# ECG_NEMO_final.net
KiCad netlist of a schematic drawn in Altium Designer
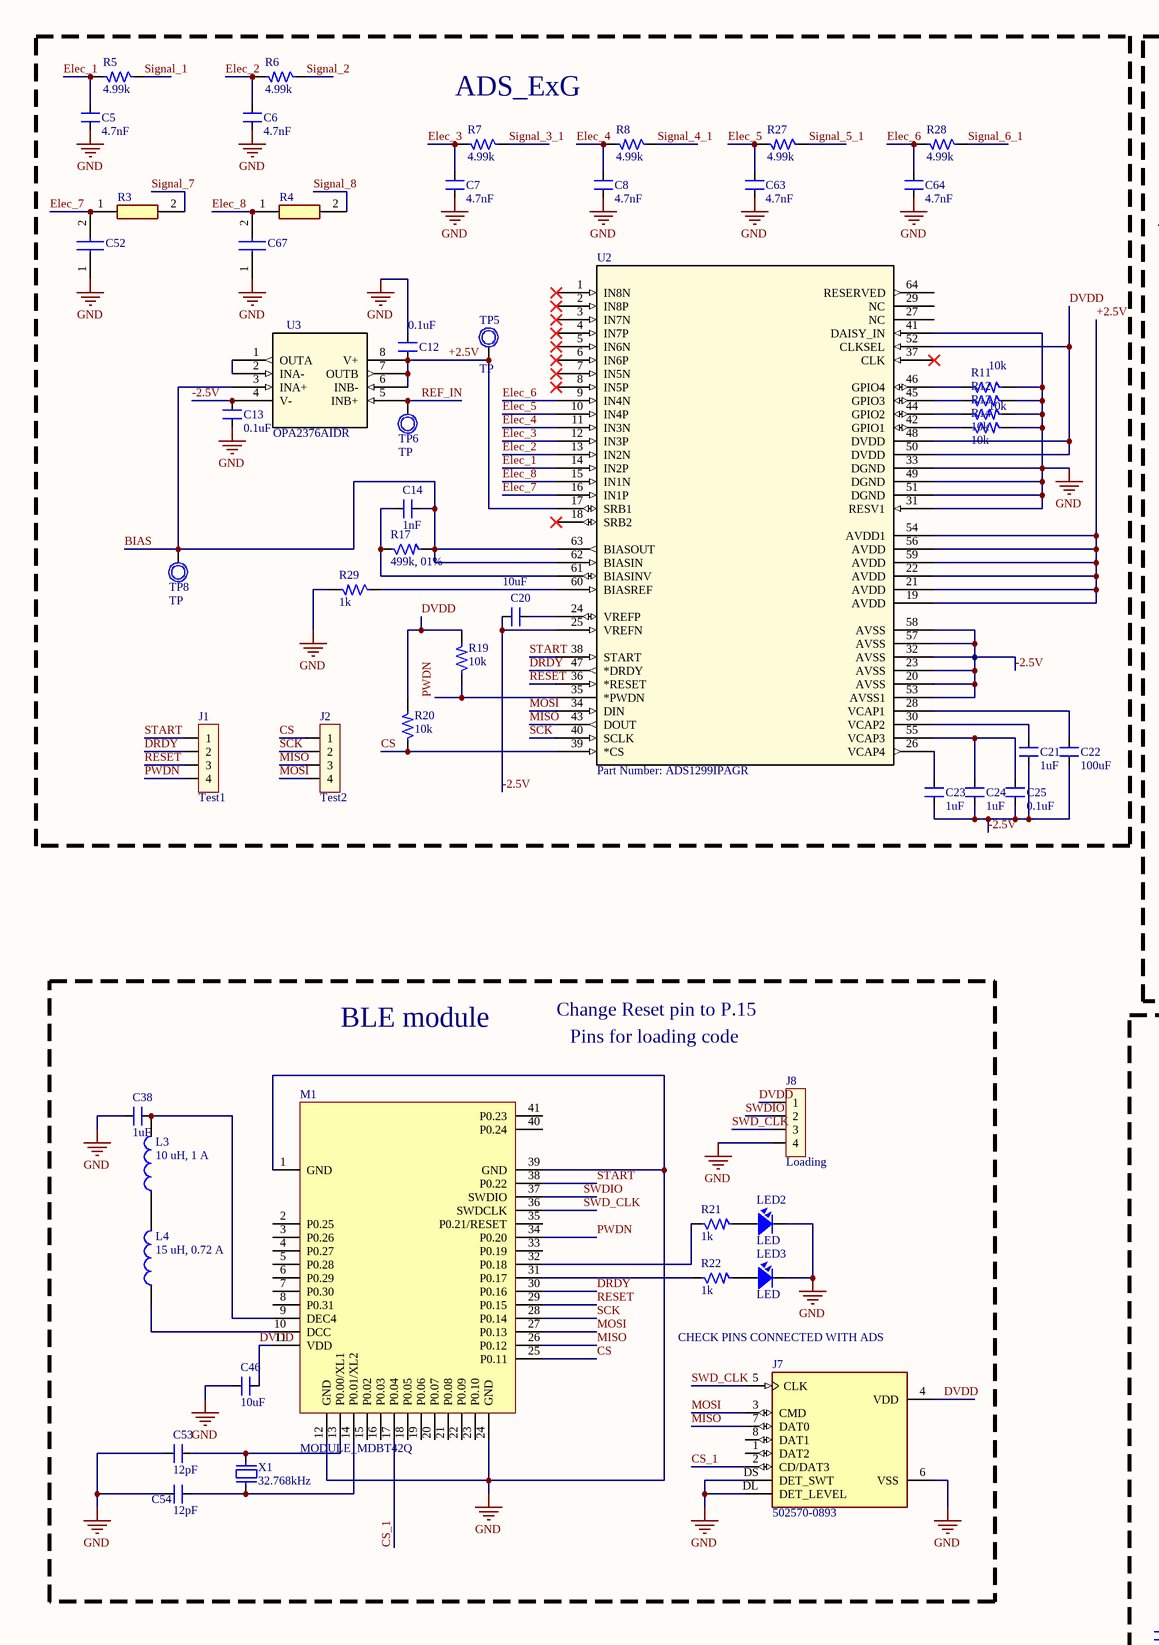
[diagram p0: ECG_NEMO_final.schdoc, left]
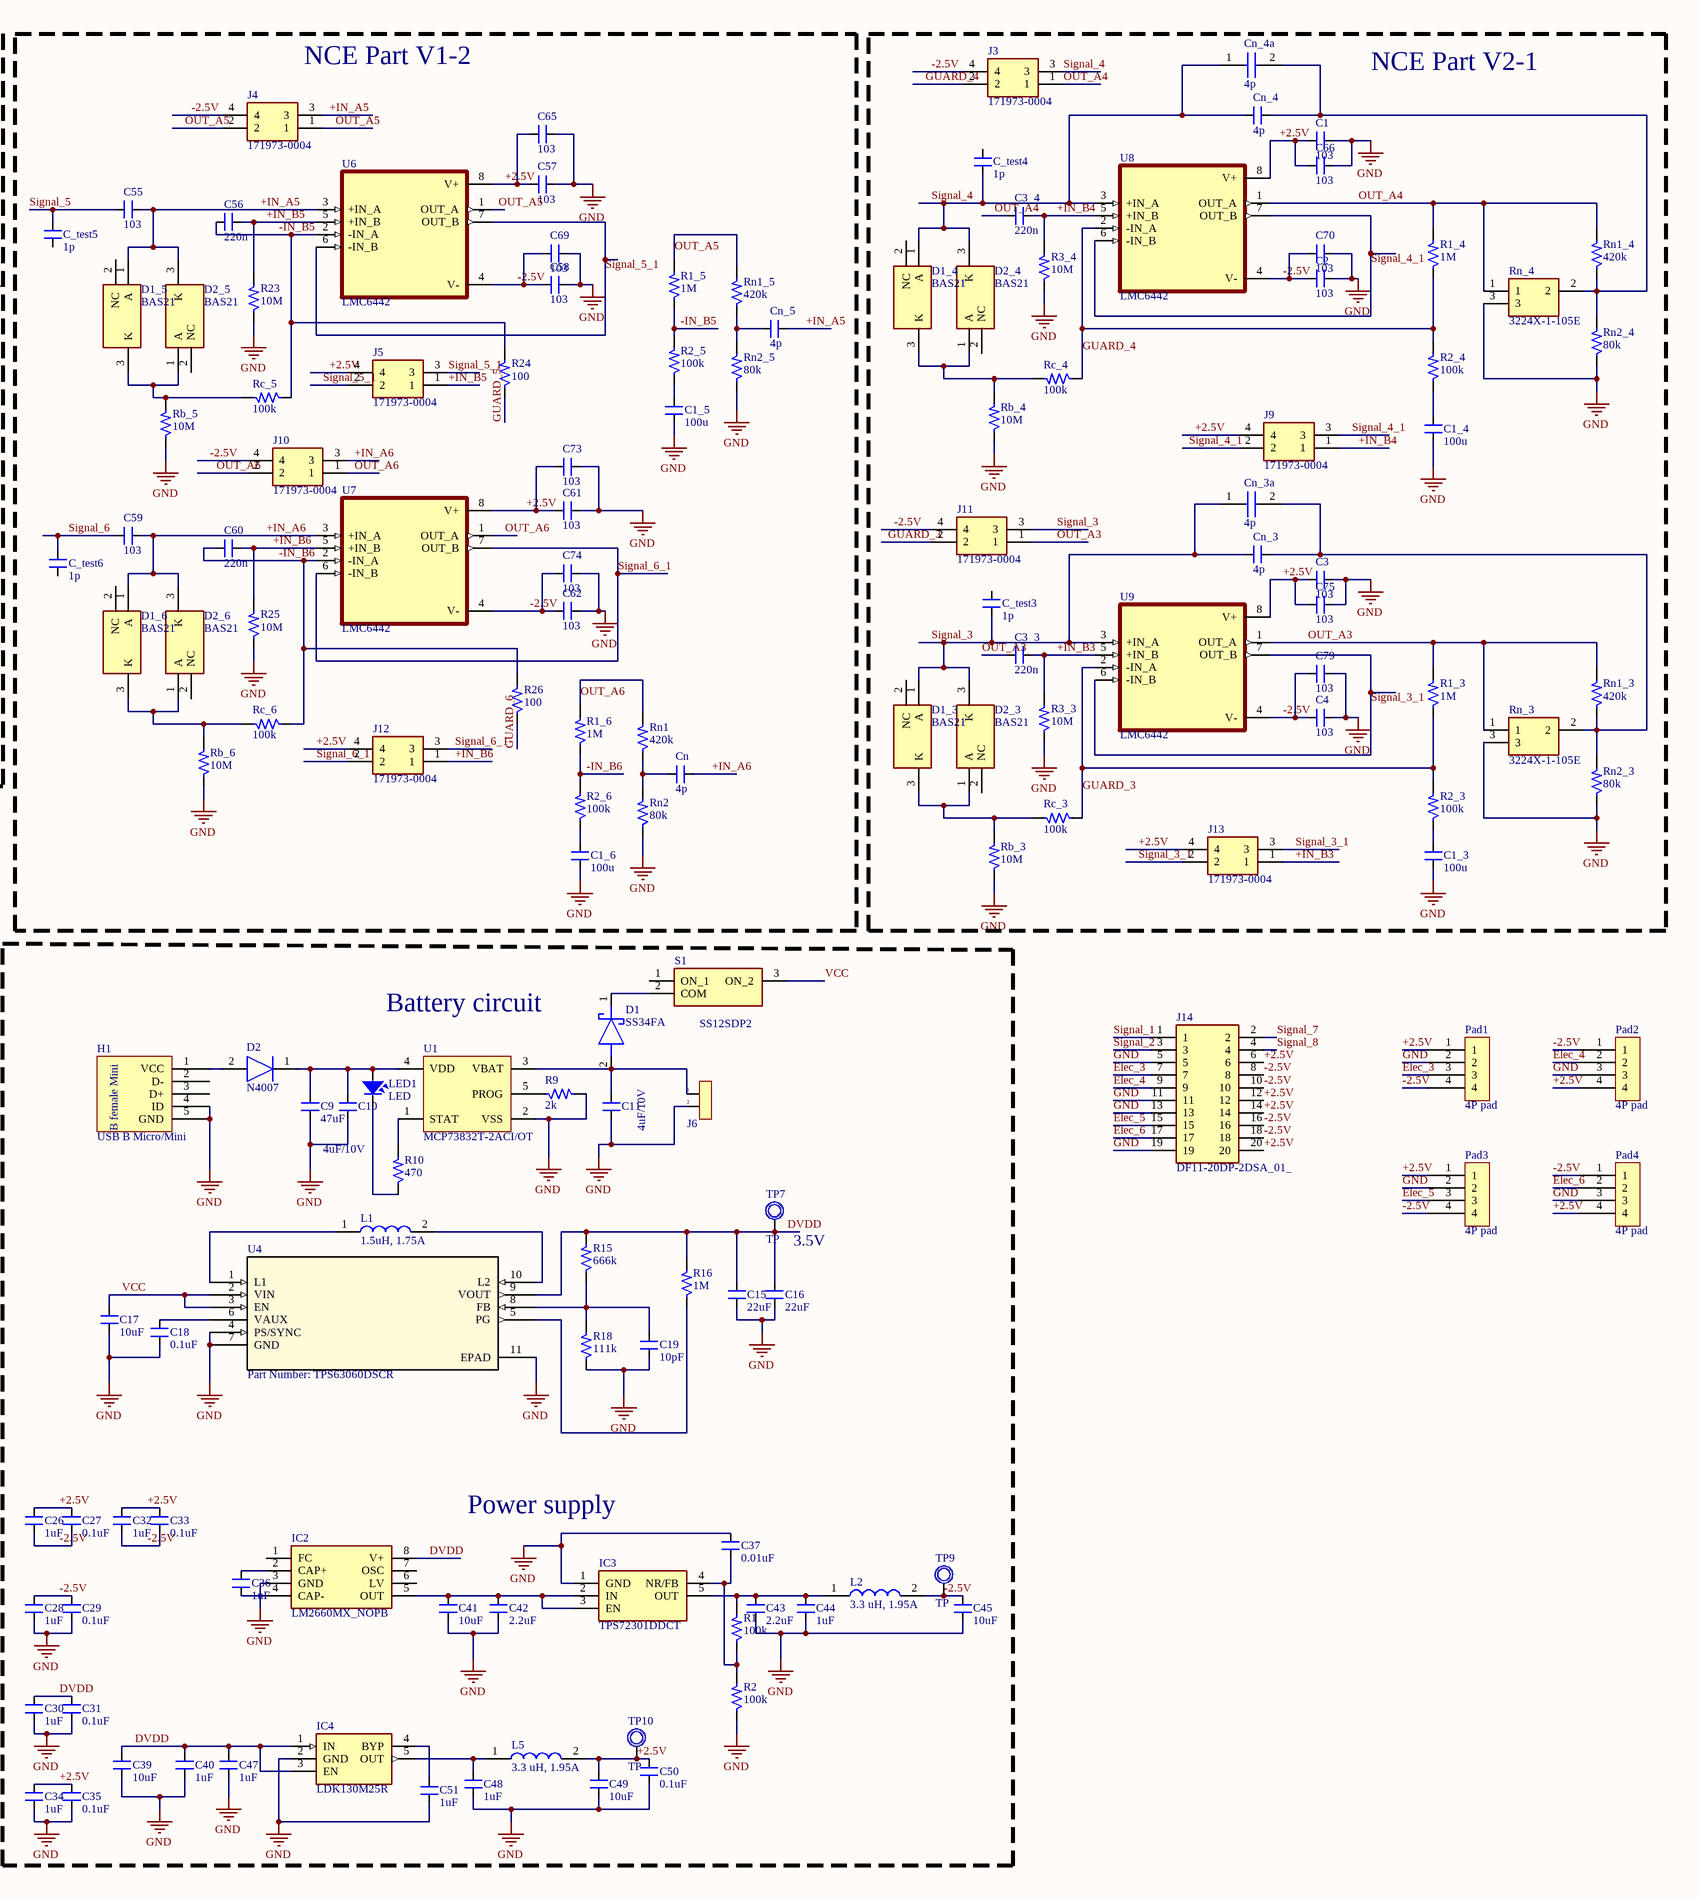
[diagram p1: ECG_NEMO_final.schdoc, right]

(export (version "E")
  (design (tool "Eeschema 10.0.6"))
  (components
    (comp (ref "C1")
      (value "103")
      (footprint "SM-0805")
      (description "Cap SMD")
      (libsource (lib "VioletofSun") (part "CM"))
    )
    (comp (ref "C1_3")
      (value "100u")
      (footprint "SM-0805")
      (description "Cap SMD")
      (libsource (lib "VioletofSun") (part "CM"))
    )
    (comp (ref "C1_4")
      (value "100u")
      (footprint "SM-0805")
      (description "Cap SMD")
      (libsource (lib "VioletofSun") (part "CM"))
    )
    (comp (ref "C1_5")
      (value "100u")
      (footprint "SM-0805")
      (description "Cap SMD")
      (libsource (lib "VioletofSun") (part "CM"))
    )
    (comp (ref "C1_6")
      (value "100u")
      (footprint "SM-0805")
      (description "Cap SMD")
      (libsource (lib "VioletofSun") (part "CM"))
    )
    (comp (ref "C2")
      (value "103")
      (footprint "SM-0805")
      (description "Cap SMD")
      (libsource (lib "VioletofSun") (part "CM"))
    )
    (comp (ref "C3")
      (value "103")
      (footprint "SM-0805")
      (description "Cap SMD")
      (libsource (lib "VioletofSun") (part "CM"))
    )
    (comp (ref "C3_3")
      (value "220n")
      (footprint "SM-0805")
      (description "Cap SMD")
      (libsource (lib "VioletofSun") (part "CM"))
    )
    (comp (ref "C3_4")
      (value "220n")
      (footprint "SM-0805")
      (description "Cap SMD")
      (libsource (lib "VioletofSun") (part "CM"))
    )
    (comp (ref "C4")
      (value "103")
      (footprint "SM-0805")
      (description "Cap SMD")
      (libsource (lib "VioletofSun") (part "CM"))
    )
    (comp (ref "C5")
      (value "4.7nF")
      (footprint "SM-0805")
      (description "Cap SMD")
      (libsource (lib "VioletofSun") (part "CM"))
    )
    (comp (ref "C6")
      (value "4.7nF")
      (footprint "SM-0805")
      (description "Cap SMD")
      (libsource (lib "VioletofSun") (part "CM"))
    )
    (comp (ref "C7")
      (value "4.7nF")
      (footprint "SM-0805")
      (description "Cap SMD")
      (libsource (lib "VioletofSun") (part "CM"))
    )
    (comp (ref "C8")
      (value "4.7nF")
      (footprint "SM-0805")
      (description "Cap SMD")
      (libsource (lib "VioletofSun") (part "CM"))
    )
    (comp (ref "C9")
      (value "47uF")
      (footprint "SM-0805")
      (description "Cap SMD")
      (libsource (lib "VioletofSun") (part "CM"))
    )
    (comp (ref "C10")
      (value "4uF/10V")
      (footprint "SM-0805")
      (description "Cap SMD")
      (libsource (lib "VioletofSun") (part "CM"))
    )
    (comp (ref "C11")
      (value "4uF/10V")
      (footprint "SM-0805")
      (description "Cap SMD")
      (libsource (lib "VioletofSun") (part "CM"))
    )
    (comp (ref "C12")
      (value "0.1uF")
      (footprint "SM-0805")
      (description "Cap SMD")
      (libsource (lib "VioletofSun") (part "CM"))
    )
    (comp (ref "C13")
      (value "0.1uF")
      (footprint "SM-0805")
      (description "Cap SMD")
      (libsource (lib "VioletofSun") (part "CM"))
    )
    (comp (ref "C14")
      (value "1nF")
      (footprint "SM-0805")
      (description "Cap SMD")
      (libsource (lib "VioletofSun") (part "CM"))
    )
    (comp (ref "C15")
      (value "22uF")
      (footprint "SM-0805")
      (description "Cap SMD")
      (libsource (lib "VioletofSun") (part "CM"))
    )
    (comp (ref "C16")
      (value "22uF")
      (footprint "SM-0805")
      (description "Cap SMD")
      (libsource (lib "VioletofSun") (part "CM"))
    )
    (comp (ref "C17")
      (value "10uF")
      (footprint "SM-0805")
      (description "Cap SMD")
      (libsource (lib "VioletofSun") (part "CM"))
    )
    (comp (ref "C18")
      (value "0.1uF")
      (footprint "SM-0805")
      (description "Cap SMD")
      (libsource (lib "VioletofSun") (part "CM"))
    )
    (comp (ref "C19")
      (value "10pF")
      (footprint "SM-0805")
      (description "Cap SMD")
      (libsource (lib "VioletofSun") (part "CM"))
    )
    (comp (ref "C20")
      (value "10uF")
      (footprint "SM-0805")
      (description "Cap SMD")
      (libsource (lib "VioletofSun") (part "CM"))
    )
    (comp (ref "C21")
      (value "1uF")
      (footprint "SM-0805")
      (description "Cap SMD")
      (libsource (lib "VioletofSun") (part "CM"))
    )
    (comp (ref "C22")
      (value "100uF")
      (footprint "SM-0805")
      (description "Cap SMD")
      (libsource (lib "VioletofSun") (part "CM"))
    )
    (comp (ref "C23")
      (value "1uF")
      (footprint "SM-0805")
      (description "Cap SMD")
      (libsource (lib "VioletofSun") (part "CM"))
    )
    (comp (ref "C24")
      (value "1uF")
      (footprint "SM-0805")
      (description "Cap SMD")
      (libsource (lib "VioletofSun") (part "CM"))
    )
    (comp (ref "C25")
      (value "0.1uF")
      (footprint "SM-0805")
      (description "Cap SMD")
      (libsource (lib "VioletofSun") (part "CM"))
    )
    (comp (ref "C26")
      (value "1uF")
      (footprint "SM-0805")
      (description "Cap SMD")
      (libsource (lib "VioletofSun") (part "CM"))
    )
    (comp (ref "C27")
      (value "0.1uF")
      (footprint "SM-0805")
      (description "Cap SMD")
      (libsource (lib "VioletofSun") (part "CM"))
    )
    (comp (ref "C28")
      (value "1uF")
      (footprint "SM-0805")
      (description "Cap SMD")
      (libsource (lib "VioletofSun") (part "CM"))
    )
    (comp (ref "C29")
      (value "0.1uF")
      (footprint "SM-0805")
      (description "Cap SMD")
      (libsource (lib "VioletofSun") (part "CM"))
    )
    (comp (ref "C30")
      (value "1uF")
      (footprint "SM-0805")
      (description "Cap SMD")
      (libsource (lib "VioletofSun") (part "CM"))
    )
    (comp (ref "C31")
      (value "0.1uF")
      (footprint "SM-0805")
      (description "Cap SMD")
      (libsource (lib "VioletofSun") (part "CM"))
    )
    (comp (ref "C32")
      (value "1uF")
      (footprint "SM-0805")
      (description "Cap SMD")
      (libsource (lib "VioletofSun") (part "CM"))
    )
    (comp (ref "C33")
      (value "0.1uF")
      (footprint "SM-0805")
      (description "Cap SMD")
      (libsource (lib "VioletofSun") (part "CM"))
    )
    (comp (ref "C34")
      (value "1uF")
      (footprint "SM-0805")
      (description "Cap SMD")
      (libsource (lib "VioletofSun") (part "CM"))
    )
    (comp (ref "C35")
      (value "0.1uF")
      (footprint "SM-0805")
      (description "Cap SMD")
      (libsource (lib "VioletofSun") (part "CM"))
    )
    (comp (ref "C36")
      (value "1uF")
      (footprint "SM-0805")
      (description "Cap SMD")
      (libsource (lib "VioletofSun") (part "CM"))
    )
    (comp (ref "C37")
      (value "0.01uF")
      (footprint "SM-0805")
      (description "Cap SMD")
      (libsource (lib "VioletofSun") (part "CM"))
    )
    (comp (ref "C38")
      (value "1uF")
      (footprint "SM-0805")
      (description "Cap SMD")
      (libsource (lib "VioletofSun") (part "CM"))
    )
    (comp (ref "C39")
      (value "10uF")
      (footprint "SM-0805")
      (description "Cap SMD")
      (libsource (lib "VioletofSun") (part "CM"))
    )
    (comp (ref "C40")
      (value "1uF")
      (footprint "SM-0805")
      (description "Cap SMD")
      (libsource (lib "VioletofSun") (part "CM"))
    )
    (comp (ref "C41")
      (value "10uF")
      (footprint "SM-0805")
      (description "Cap SMD")
      (libsource (lib "VioletofSun") (part "CM"))
    )
    (comp (ref "C42")
      (value "2.2uF")
      (footprint "SM-0805")
      (description "Cap SMD")
      (libsource (lib "VioletofSun") (part "CM"))
    )
    (comp (ref "C43")
      (value "2.2uF")
      (footprint "SM-0805")
      (description "Cap SMD")
      (libsource (lib "VioletofSun") (part "CM"))
    )
    (comp (ref "C44")
      (value "1uF")
      (footprint "SM-0805")
      (description "Cap SMD")
      (libsource (lib "VioletofSun") (part "CM"))
    )
    (comp (ref "C45")
      (value "10uF")
      (footprint "SM-0805")
      (description "Cap SMD")
      (libsource (lib "VioletofSun") (part "CM"))
    )
    (comp (ref "C46")
      (value "10uF")
      (footprint "SM-0805")
      (description "Cap SMD")
      (libsource (lib "VioletofSun") (part "CM"))
    )
    (comp (ref "C47")
      (value "1uF")
      (footprint "SM-0805")
      (description "Cap SMD")
      (libsource (lib "VioletofSun") (part "CM"))
    )
    (comp (ref "C48")
      (value "1uF")
      (footprint "SM-0805")
      (description "Cap SMD")
      (libsource (lib "VioletofSun") (part "CM"))
    )
    (comp (ref "C49")
      (value "10uF")
      (footprint "SM-0805")
      (description "Cap SMD")
      (libsource (lib "VioletofSun") (part "CM"))
    )
    (comp (ref "C50")
      (value "0.1uF")
      (footprint "SM-0805")
      (description "Cap SMD")
      (libsource (lib "VioletofSun") (part "CM"))
    )
    (comp (ref "C51")
      (value "1uF")
      (footprint "SM-0805")
      (description "Cap SMD")
      (libsource (lib "VioletofSun") (part "CM"))
    )
    (comp (ref "C52")
      (value "VJ0805Y472KXAMC")
      (footprint "SamacSys:CAPC2012X145N")
      (description "Capacitor 4.7nF")
      (fields (field (name "MOUSER PART NUMBER") "77-VJ0805Y472KXAMC"))
      (libsource (lib "SamacSys") (part "VJ0805Y472KXAMC"))
    )
    (comp (ref "C53")
      (value "12pF")
      (footprint "SM-0805")
      (description "Cap SMD")
      (libsource (lib "VioletofSun") (part "CM"))
    )
    (comp (ref "C54")
      (value "12pF")
      (footprint "SM-0805")
      (description "Cap SMD")
      (libsource (lib "VioletofSun") (part "CM"))
    )
    (comp (ref "C55")
      (value "103")
      (footprint "SM-0805")
      (description "Cap SMD")
      (libsource (lib "Free Documents") (part "CM_5"))
    )
    (comp (ref "C56")
      (value "220n")
      (footprint "SM-0805")
      (description "Cap SMD")
      (libsource (lib "VioletofSun") (part "CM"))
    )
    (comp (ref "C57")
      (value "103")
      (footprint "SM-0805")
      (description "Cap SMD")
      (libsource (lib "VioletofSun") (part "CM"))
    )
    (comp (ref "C58")
      (value "103")
      (footprint "SM-0805")
      (description "Cap SMD")
      (libsource (lib "VioletofSun") (part "CM"))
    )
    (comp (ref "C59")
      (value "103")
      (footprint "SM-0805")
      (description "Cap SMD")
      (libsource (lib "VioletofSun") (part "CM"))
    )
    (comp (ref "C60")
      (value "220n")
      (footprint "SM-0805")
      (description "Cap SMD")
      (libsource (lib "VioletofSun") (part "CM"))
    )
    (comp (ref "C61")
      (value "103")
      (footprint "SM-0805")
      (description "Cap SMD")
      (libsource (lib "VioletofSun") (part "CM"))
    )
    (comp (ref "C62")
      (value "103")
      (footprint "SM-0805")
      (description "Cap SMD")
      (libsource (lib "VioletofSun") (part "CM"))
    )
    (comp (ref "C63")
      (value "4.7nF")
      (footprint "SM-0805")
      (description "Cap SMD")
      (libsource (lib "VioletofSun") (part "CM"))
    )
    (comp (ref "C64")
      (value "4.7nF")
      (footprint "SM-0805")
      (description "Cap SMD")
      (libsource (lib "VioletofSun") (part "CM"))
    )
    (comp (ref "C65")
      (value "103")
      (footprint "SM-0805")
      (description "Cap SMD")
      (libsource (lib "VioletofSun") (part "CM"))
    )
    (comp (ref "C66")
      (value "103")
      (footprint "SM-0805")
      (description "Cap SMD")
      (libsource (lib "VioletofSun") (part "CM"))
    )
    (comp (ref "C67")
      (value "VJ0805Y472KXAMC")
      (footprint "SamacSys:CAPC2012X145N")
      (description "Capacitor 4.7nF")
      (fields (field (name "MOUSER PART NUMBER") "77-VJ0805Y472KXAMC"))
      (libsource (lib "SamacSys") (part "VJ0805Y472KXAMC"))
    )
    (comp (ref "C69")
      (value "103")
      (footprint "SM-0805")
      (description "Cap SMD")
      (libsource (lib "VioletofSun") (part "CM"))
    )
    (comp (ref "C70")
      (value "103")
      (footprint "SM-0805")
      (description "Cap SMD")
      (libsource (lib "VioletofSun") (part "CM"))
    )
    (comp (ref "C73")
      (value "103")
      (footprint "SM-0805")
      (description "Cap SMD")
      (libsource (lib "VioletofSun") (part "CM"))
    )
    (comp (ref "C74")
      (value "103")
      (footprint "SM-0805")
      (description "Cap SMD")
      (libsource (lib "VioletofSun") (part "CM"))
    )
    (comp (ref "C75")
      (value "103")
      (footprint "SM-0805")
      (description "Cap SMD")
      (libsource (lib "VioletofSun") (part "CM"))
    )
    (comp (ref "C79")
      (value "103")
      (footprint "SM-0805")
      (description "Cap SMD")
      (libsource (lib "VioletofSun") (part "CM"))
    )
    (comp (ref "Cn")
      (value "4p")
      (footprint "SM-0805")
      (description "Cap SMD")
      (libsource (lib "VioletofSun") (part "CM"))
    )
    (comp (ref "Cn_3")
      (value "4p")
      (footprint "SM-0805")
      (description "Cap SMD")
      (libsource (lib "VioletofSun") (part "CM"))
    )
    (comp (ref "Cn_3a")
      (value "4p")
      (footprint "Var_Cap-JZ100:JZ100")
      (description "Capacitor")
      (fields
        (field (name "MANUFACTURER_PART_NUMBER") "JZ100")
        (field (name "MOUSER PART NUMBER") "768-JZ100")
      )
      (libsource (lib "Var_Cap-JZ100") (part "JZ100"))
    )
    (comp (ref "Cn_4")
      (value "4p")
      (footprint "SM-0805")
      (description "Cap SMD")
      (libsource (lib "VioletofSun") (part "CM"))
    )
    (comp (ref "Cn_4a")
      (value "4p")
      (footprint "Var_Cap-JZ100:JZ100")
      (description "Capacitor")
      (fields
        (field (name "MANUFACTURER_PART_NUMBER") "JZ100")
        (field (name "MOUSER PART NUMBER") "768-JZ100")
      )
      (libsource (lib "Var_Cap-JZ100") (part "JZ100"))
    )
    (comp (ref "Cn_5")
      (value "4p")
      (footprint "SM-0805")
      (description "Cap SMD")
      (libsource (lib "VioletofSun") (part "CM"))
    )
    (comp (ref "C_test3")
      (value "1p")
      (footprint "SM-0805")
      (description "Cap SMD")
      (libsource (lib "Flex-PCB-fmECG") (part "CM_5"))
    )
    (comp (ref "C_test4")
      (value "1p")
      (footprint "SM-0805")
      (description "Cap SMD")
      (libsource (lib "Flex-PCB-fmECG") (part "CM_5"))
    )
    (comp (ref "C_test5")
      (value "1p")
      (footprint "SM-0805")
      (description "Cap SMD")
      (libsource (lib "Flex-PCB-fmECG") (part "CM_5"))
    )
    (comp (ref "C_test6")
      (value "1p")
      (footprint "SM-0805")
      (description "Cap SMD")
      (libsource (lib "Flex-PCB-fmECG") (part "CM_5"))
    )
    (comp (ref "D1")
      (value "SS34FA")
      (footprint "SODFL3618X143N")
      (description "Schottky Diode")
      (fields (field (name "MOUSER PART NUMBER") "512-SS34FA"))
      (libsource (lib "*") (part "SS34FA"))
    )
    (comp (ref "D1_3")
      (value "BAS21")
      (footprint "BAS21:SOT95P240X120-3N")
      (description "Diode")
      (fields (field (name "MOUSER PART NUMBER") "512-BAS21"))
      (libsource (lib "") (part "BAS21_1"))
    )
    (comp (ref "D1_4")
      (value "BAS21")
      (footprint "BAS21:SOT95P240X120-3N")
      (description "Diode")
      (fields (field (name "MOUSER PART NUMBER") "512-BAS21"))
      (libsource (lib "") (part "BAS21_1"))
    )
    (comp (ref "D1_5")
      (value "BAS21")
      (footprint "BAS21:SOT95P240X120-3N")
      (description "Diode")
      (fields (field (name "MOUSER PART NUMBER") "512-BAS21"))
      (libsource (lib "") (part "BAS21_1"))
    )
    (comp (ref "D1_6")
      (value "BAS21")
      (footprint "BAS21:SOT95P240X120-3N")
      (description "Diode")
      (fields (field (name "MOUSER PART NUMBER") "512-BAS21"))
      (libsource (lib "") (part "BAS21_1"))
    )
    (comp (ref "D2")
      (value "N4007")
      (footprint "DIOM5025X220N")
      (description "Diode")
      (fields
        (field (name "MOUSER PART NUMBER") "346-EC11FS2")
        (field (name "MANUFACTURER_PART_NUMBER") "EC11FS2")
      )
      (libsource (lib "*") (part "EC11FS2"))
    )
    (comp (ref "D2_3")
      (value "BAS21")
      (footprint "BAS21:SOT95P240X120-3N")
      (description "Diode")
      (fields (field (name "MOUSER PART NUMBER") "512-BAS21"))
      (libsource (lib "BAS21") (part "BAS21"))
    )
    (comp (ref "D2_4")
      (value "BAS21")
      (footprint "BAS21:SOT95P240X120-3N")
      (description "Diode")
      (fields (field (name "MOUSER PART NUMBER") "512-BAS21"))
      (libsource (lib "BAS21") (part "BAS21"))
    )
    (comp (ref "D2_5")
      (value "BAS21")
      (footprint "BAS21:SOT95P240X120-3N")
      (description "Diode")
      (fields (field (name "MOUSER PART NUMBER") "512-BAS21"))
      (libsource (lib "BAS21") (part "BAS21"))
    )
    (comp (ref "D2_6")
      (value "BAS21")
      (footprint "BAS21:SOT95P240X120-3N")
      (description "Diode")
      (fields (field (name "MOUSER PART NUMBER") "512-BAS21"))
      (libsource (lib "BAS21") (part "BAS21"))
    )
    (comp (ref "H1")
      (value "USB B Micro/Mini")
      (footprint "USB-B-MICRO-female Tai02")
      (description "USB B Female Micro/Mini SMD")
      (libsource (lib "mylib") (part "USB B Female Micro/Mini SMD"))
    )
    (comp (ref "IC2")
      (value "LM2660MX_NOPB")
      (footprint "LM2660MX:SOIC127P600X175-8N")
      (description "Integrated Circuit")
      (fields (field (name "MANUFACTURER_PART_NUMBER") "LM2660MX NOPB"))
      (libsource (lib "LM2660MX") (part "LM2660MX_NOPB"))
    )
    (comp (ref "IC3")
      (value "TPS72301DDCT")
      (footprint "TPS72301DDCT:SOT95P280X110-5N")
      (description "Integrated Circuit")
      (fields (field (name "MOUSER PART NUMBER") "595-TPS72301DDCT"))
      (libsource (lib "TPS72301DDCT") (part "TPS72301DDCT"))
    )
    (comp (ref "IC4")
      (value "LDK130M25R")
      (footprint "LDK130M25R:SOT95P280X145-5N")
      (description "Integrated Circuit")
      (fields (field (name "MOUSER PART NUMBER") "511-LDK130M25R"))
      (libsource (lib "LDK130M25R") (part "LDK130M25R"))
    )
    (comp (ref "J1")
      (value "Test1")
      (footprint "sip4")
      (description "Connector 4")
      (libsource (lib "VioletofSun") (part "JP4"))
    )
    (comp (ref "J2")
      (value "Test2")
      (footprint "sip4")
      (description "Connector 4")
      (libsource (lib "VioletofSun") (part "JP4"))
    )
    (comp (ref "J3")
      (value "171973-0004")
      (footprint "Head4_SMD:1719730004")
      (description "Connector")
      (fields (field (name "MOUSER PART NUMBER") "538-171973-0004"))
      (libsource (lib "Head4_SMD") (part "171973-0004"))
    )
    (comp (ref "J4")
      (value "171973-0004")
      (footprint "Head4_SMD:1719730004")
      (description "Connector")
      (fields (field (name "MOUSER PART NUMBER") "538-171973-0004"))
      (libsource (lib "Head4_SMD") (part "171973-0004"))
    )
    (comp (ref "J5")
      (value "171973-0004")
      (footprint "Head4_SMD:1719730004")
      (description "Connector")
      (fields (field (name "MOUSER PART NUMBER") "538-171973-0004"))
      (libsource (lib "Head4_SMD") (part "171973-0004"))
    )
    (comp (ref "J6")
      (value "Jumper 2")
      (footprint "J2_Jst SH_1mm")
      (libsource (lib "VioletofSun") (part "JP 2"))
    )
    (comp (ref "J7")
      (value "502570-0893")
      (footprint "MOLEX_502570-0893")
      (description "10 _8 + 2_ Position Card Connector Secure Digital - microSDâ„¢ Surface Mount, Right Angle Gold")
      (fields (field (name "MF") "Molex"))
      (libsource (lib "502570-0893") (part "502570-0893"))
    )
    (comp (ref "J8")
      (value "Loading")
      (footprint "sip4")
      (description "Connector 4")
      (libsource (lib "VioletofSun") (part "JP4"))
    )
    (comp (ref "J9")
      (value "171973-0004")
      (footprint "Head4_SMD:1719730004")
      (description "Connector")
      (fields (field (name "MOUSER PART NUMBER") "538-171973-0004"))
      (libsource (lib "Head4_SMD") (part "171973-0004"))
    )
    (comp (ref "J10")
      (value "171973-0004")
      (footprint "Head4_SMD:1719730004")
      (description "Connector")
      (fields (field (name "MOUSER PART NUMBER") "538-171973-0004"))
      (libsource (lib "Head4_SMD") (part "171973-0004"))
    )
    (comp (ref "J11")
      (value "171973-0004")
      (footprint "Head4_SMD:1719730004")
      (description "Connector")
      (fields (field (name "MOUSER PART NUMBER") "538-171973-0004"))
      (libsource (lib "Head4_SMD") (part "171973-0004"))
    )
    (comp (ref "J12")
      (value "171973-0004")
      (footprint "Head4_SMD:1719730004")
      (description "Connector")
      (fields (field (name "MOUSER PART NUMBER") "538-171973-0004"))
      (libsource (lib "Head4_SMD") (part "171973-0004"))
    )
    (comp (ref "J13")
      (value "171973-0004")
      (footprint "Head4_SMD:1719730004")
      (description "Connector")
      (fields (field (name "MOUSER PART NUMBER") "538-171973-0004"))
      (libsource (lib "Head4_SMD") (part "171973-0004"))
    )
    (comp (ref "J14")
      (value "DF11-20DP-2DSA_01_")
      (footprint "20P 2.5mm")
      (description "Connector")
      (fields
        (field (name "MANUFACTURER_PART_NUMBER") "DF11-20DP-2DSA(01)")
        (field (name "MOUSER PART NUMBER") "798-DF11-20DP-2DSA01")
      )
      (libsource (lib "SamacSys") (part "DF11-20DP-2DSA_01_"))
    )
    (comp (ref "L1")
      (value "1.5uH, 1.75A")
      (footprint "744031001:WE-TPC_381692")
      (description "Inductor")
      (fields
        (field (name "MANUFACTURER_PART_NUMBER") "744031001")
        (field (name "MOUSER PART NUMBER") "710-744031001")
      )
      (libsource (lib "744031001") (part "744031001"))
    )
    (comp (ref "L2")
      (value "3.3 uH, 1.95A")
      (footprint "Inductor-744042003:WE-TPC_4818/482892")
      (description "Inductor")
      (fields
        (field (name "MANUFACTURER_PART_NUMBER") "744042003")
        (field (name "MOUSER PART NUMBER") "710-744042003")
      )
      (libsource (lib "Inductor-744042003") (part "744042003"))
    )
    (comp (ref "L3")
      (value "10 uH, 1 A")
      (footprint "WE-TPC_2828")
      (description "SMT Shielded Tiny Power Inductor WE-TPC, size 2828, 10 uH, 1 A")
      (fields (field (name "PART NUMBER") "744025100") (field (name "PUBLISHER") "Wurth Elektronik"))
      (libsource (lib "ALTIUM-WE-TPC-rev18a") (part "744025100"))
    )
    (comp (ref "L4")
      (value "15 uH, 0.72 A")
      (footprint "WE-TPC_2828")
      (description "SMT Shielded Tiny Power Inductor WE-TPC, size 2828, 15 uH, 0.72 A")
      (fields (field (name "PART NUMBER") "744025150") (field (name "PUBLISHER") "Wurth Elektronik"))
      (libsource (lib "ALTIUM-WE-TPC-rev18a") (part "744025150"))
    )
    (comp (ref "L5")
      (value "3.3 uH, 1.95A")
      (footprint "Inductor-744042003:WE-TPC_4818/482892")
      (description "Inductor")
      (fields
        (field (name "MANUFACTURER_PART_NUMBER") "744042003")
        (field (name "MOUSER PART NUMBER") "710-744042003")
      )
      (libsource (lib "Inductor-744042003") (part "744042003"))
    )
    (comp (ref "LED1")
      (value "LED")
      (footprint "SM-0805")
      (description "LED Single colour Green and Red")
      (libsource (lib "") (part "LED_1"))
    )
    (comp (ref "LED2")
      (value "LED")
      (footprint "led0805")
      (description "LED Single colour Green and Red")
      (libsource (lib "VioletofSun") (part "LED"))
    )
    (comp (ref "LED3")
      (value "LED")
      (footprint "led0805")
      (description "LED Single colour Green and Red")
      (libsource (lib "VioletofSun") (part "LED"))
    )
    (comp (ref "M1")
      (value "MODULE_MDBT42Q")
      (footprint "PCB_MDBT42Q_10X16")
      (description "MDBT42Q")
      (libsource (lib "MDBT42Q_SCHLIB_181015") (part "MODULE_MDBT42Q"))
    )
    (comp (ref "Pad1") (value "4P pad") (footprint "04P 2.5mm") (libsource (lib "SamacSys") (part "4P pad")))
    (comp (ref "Pad2") (value "4P pad") (footprint "04P 2.5mm") (libsource (lib "SamacSys") (part "4P pad")))
    (comp (ref "Pad3") (value "4P pad") (footprint "04P 2.5mm") (libsource (lib "SamacSys") (part "4P pad")))
    (comp (ref "Pad4") (value "4P pad") (footprint "04P 2.5mm") (libsource (lib "SamacSys") (part "4P pad")))
    (comp (ref "R1")
      (value "100k")
      (footprint "SM-0805")
      (description "Resistor 1/4W")
      (libsource (lib "PCB_NEMO_v1-2_v2-1") (part "R"))
    )
    (comp (ref "R1_3")
      (value "1M")
      (footprint "SM-0805")
      (description "Resistor 1/4W")
      (libsource (lib "VioletofSun") (part "R"))
    )
    (comp (ref "R1_4")
      (value "1M")
      (footprint "SM-0805")
      (description "Resistor 1/4W")
      (libsource (lib "VioletofSun") (part "R"))
    )
    (comp (ref "R1_5")
      (value "1M")
      (footprint "SM-0805")
      (description "Resistor 1/4W")
      (libsource (lib "VioletofSun") (part "R"))
    )
    (comp (ref "R1_6")
      (value "1M")
      (footprint "SM-0805")
      (description "Resistor 1/4W")
      (libsource (lib "VioletofSun") (part "R"))
    )
    (comp (ref "R2")
      (value "100k")
      (footprint "SM-0805")
      (description "Resistor 1/4W")
      (libsource (lib "PCB_NEMO_v1-2_v2-1") (part "R"))
    )
    (comp (ref "R2_3")
      (value "100k")
      (footprint "SM-0805")
      (description "Resistor 1/4W")
      (libsource (lib "VioletofSun") (part "R"))
    )
    (comp (ref "R2_4")
      (value "100k")
      (footprint "SM-0805")
      (description "Resistor 1/4W")
      (libsource (lib "VioletofSun") (part "R"))
    )
    (comp (ref "R2_5")
      (value "100k")
      (footprint "SM-0805")
      (description "Resistor 1/4W")
      (libsource (lib "VioletofSun") (part "R"))
    )
    (comp (ref "R2_6")
      (value "100k")
      (footprint "SM-0805")
      (description "Resistor 1/4W")
      (libsource (lib "VioletofSun") (part "R"))
    )
    (comp (ref "R3")
      (value "ERJ-HP6D4991V")
      (footprint "SamacSys:ERJHP6D1000V")
      (description "Resistor 4.99k")
      (libsource (lib "SamacSys") (part "ERJ-HP6D4991V"))
    )
    (comp (ref "R3_3")
      (value "10M")
      (footprint "SM-0805")
      (description "Resistor 1/4W")
      (libsource (lib "VioletofSun") (part "R"))
    )
    (comp (ref "R3_4")
      (value "10M")
      (footprint "SM-0805")
      (description "Resistor 1/4W")
      (libsource (lib "VioletofSun") (part "R"))
    )
    (comp (ref "R4")
      (value "ERJ-HP6D4991V")
      (footprint "SamacSys:ERJHP6D1000V")
      (description "Resistor 4.99k")
      (libsource (lib "SamacSys") (part "ERJ-HP6D4991V"))
    )
    (comp (ref "R5")
      (value "4.99k")
      (footprint "SM-0805")
      (description "Resistor 1/4W")
      (libsource (lib "VioletofSun") (part "R"))
    )
    (comp (ref "R6")
      (value "4.99k")
      (footprint "SM-0805")
      (description "Resistor 1/4W")
      (libsource (lib "VioletofSun") (part "R"))
    )
    (comp (ref "R7")
      (value "4.99k")
      (footprint "SM-0805")
      (description "Resistor 1/4W")
      (libsource (lib "VioletofSun") (part "R"))
    )
    (comp (ref "R8")
      (value "4.99k")
      (footprint "SM-0805")
      (description "Resistor 1/4W")
      (libsource (lib "VioletofSun") (part "R"))
    )
    (comp (ref "R9")
      (value "2k")
      (footprint "SM-0805")
      (description "Resistor 1/4W")
      (libsource (lib "VioletofSun") (part "R"))
    )
    (comp (ref "R10")
      (value "470")
      (footprint "SM-0805")
      (description "Resistor 1/4W")
      (libsource (lib "VioletofSun") (part "R"))
    )
    (comp (ref "R11")
      (value "10k")
      (footprint "SM-0805")
      (description "Resistor 1/4W")
      (libsource (lib "VioletofSun") (part "R"))
    )
    (comp (ref "R12")
      (value "10k")
      (footprint "SM-0805")
      (description "Resistor 1/4W")
      (libsource (lib "VioletofSun") (part "R"))
    )
    (comp (ref "R13")
      (value "10k")
      (footprint "SM-0805")
      (description "Resistor 1/4W")
      (libsource (lib "VioletofSun") (part "R"))
    )
    (comp (ref "R14")
      (value "10k")
      (footprint "SM-0805")
      (description "Resistor 1/4W")
      (libsource (lib "VioletofSun") (part "R"))
    )
    (comp (ref "R15")
      (value "666k")
      (footprint "SM-0805")
      (description "Resistor 1/4W")
      (libsource (lib "VioletofSun") (part "R"))
    )
    (comp (ref "R16")
      (value "1M")
      (footprint "SM-0805")
      (description "Resistor 1/4W")
      (libsource (lib "VioletofSun") (part "R"))
    )
    (comp (ref "R17")
      (value "499k, 01%")
      (footprint "SM-0805")
      (description "Resistor 1/4W")
      (libsource (lib "VioletofSun") (part "R"))
    )
    (comp (ref "R18")
      (value "111k")
      (footprint "SM-0805")
      (description "Resistor 1/4W")
      (libsource (lib "VioletofSun") (part "R"))
    )
    (comp (ref "R19")
      (value "10k")
      (footprint "SM-0805")
      (description "Resistor 1/4W")
      (libsource (lib "VioletofSun") (part "R"))
    )
    (comp (ref "R20")
      (value "10k")
      (footprint "SM-0805")
      (description "Resistor 1/4W")
      (libsource (lib "VioletofSun") (part "R"))
    )
    (comp (ref "R21")
      (value "1k")
      (footprint "SM-0805")
      (description "Resistor 1/4W")
      (libsource (lib "VioletofSun") (part "R"))
    )
    (comp (ref "R22")
      (value "1k")
      (footprint "SM-0805")
      (description "Resistor 1/4W")
      (libsource (lib "VioletofSun") (part "R"))
    )
    (comp (ref "R23")
      (value "10M")
      (footprint "SM-0805")
      (description "Resistor 1/4W")
      (libsource (lib "VioletofSun") (part "R"))
    )
    (comp (ref "R24")
      (value "100")
      (footprint "SM-0805")
      (description "Resistor 1/4W")
      (libsource (lib "VioletofSun") (part "R"))
    )
    (comp (ref "R25")
      (value "10M")
      (footprint "SM-0805")
      (description "Resistor 1/4W")
      (libsource (lib "VioletofSun") (part "R"))
    )
    (comp (ref "R26")
      (value "100")
      (footprint "SM-0805")
      (description "Resistor 1/4W")
      (libsource (lib "VioletofSun") (part "R"))
    )
    (comp (ref "R27")
      (value "4.99k")
      (footprint "SM-0805")
      (description "Resistor 1/4W")
      (libsource (lib "VioletofSun") (part "R"))
    )
    (comp (ref "R28")
      (value "4.99k")
      (footprint "SM-0805")
      (description "Resistor 1/4W")
      (libsource (lib "VioletofSun") (part "R"))
    )
    (comp (ref "R29")
      (value "1k")
      (footprint "SM-0805")
      (description "Resistor 1/4W")
      (libsource (lib "VioletofSun") (part "R"))
    )
    (comp (ref "Rb_3")
      (value "10M")
      (footprint "SM-0805")
      (description "Resistor 1/4W")
      (libsource (lib "VioletofSun") (part "R"))
    )
    (comp (ref "Rb_4")
      (value "10M")
      (footprint "SM-0805")
      (description "Resistor 1/4W")
      (libsource (lib "VioletofSun") (part "R"))
    )
    (comp (ref "Rb_5")
      (value "10M")
      (footprint "SM-0805")
      (description "Resistor 1/4W")
      (libsource (lib "VioletofSun") (part "R"))
    )
    (comp (ref "Rb_6")
      (value "10M")
      (footprint "SM-0805")
      (description "Resistor 1/4W")
      (libsource (lib "VioletofSun") (part "R"))
    )
    (comp (ref "Rc_3")
      (value "100k")
      (footprint "SM-0805")
      (description "Resistor 1/4W")
      (libsource (lib "VioletofSun") (part "R"))
    )
    (comp (ref "Rc_4")
      (value "100k")
      (footprint "SM-0805")
      (description "Resistor 1/4W")
      (libsource (lib "VioletofSun") (part "R"))
    )
    (comp (ref "Rc_5")
      (value "100k")
      (footprint "SM-0805")
      (description "Resistor 1/4W")
      (libsource (lib "VioletofSun") (part "R"))
    )
    (comp (ref "Rc_6")
      (value "100k")
      (footprint "SM-0805")
      (description "Resistor 1/4W")
      (libsource (lib "VioletofSun") (part "R"))
    )
    (comp (ref "Rn1")
      (value "420k")
      (footprint "SM-0805")
      (description "Resistor 1/4W")
      (libsource (lib "VioletofSun") (part "R"))
    )
    (comp (ref "Rn1_3")
      (value "420k")
      (footprint "SM-0805")
      (description "Resistor 1/4W")
      (libsource (lib "VioletofSun") (part "R"))
    )
    (comp (ref "Rn1_4")
      (value "420k")
      (footprint "SM-0805")
      (description "Resistor 1/4W")
      (libsource (lib "VioletofSun") (part "R"))
    )
    (comp (ref "Rn1_5")
      (value "420k")
      (footprint "SM-0805")
      (description "Resistor 1/4W")
      (libsource (lib "VioletofSun") (part "R"))
    )
    (comp (ref "Rn2")
      (value "80k")
      (footprint "SM-0805")
      (description "Resistor 1/4W")
      (libsource (lib "VioletofSun") (part "R"))
    )
    (comp (ref "Rn2_3")
      (value "80k")
      (footprint "SM-0805")
      (description "Resistor 1/4W")
      (libsource (lib "VioletofSun") (part "R"))
    )
    (comp (ref "Rn2_4")
      (value "80k")
      (footprint "SM-0805")
      (description "Resistor 1/4W")
      (libsource (lib "VioletofSun") (part "R"))
    )
    (comp (ref "Rn2_5")
      (value "80k")
      (footprint "SM-0805")
      (description "Resistor 1/4W")
      (libsource (lib "VioletofSun") (part "R"))
    )
    (comp (ref "Rn_3")
      (value "3224X-1-105E")
      (footprint "3224X-1-504E:3224X1502E")
      (description "Resistor")
      (fields (field (name "MOUSER PART NUMBER") "652-3224X-1-105E"))
      (libsource (lib "3224X-1-504E") (part "3224X-1-105E"))
    )
    (comp (ref "Rn_4")
      (value "3224X-1-105E")
      (footprint "3224X-1-504E:3224X1502E")
      (description "Resistor")
      (fields (field (name "MOUSER PART NUMBER") "652-3224X-1-105E"))
      (libsource (lib "3224X-1-504E") (part "3224X-1-105E"))
    )
    (comp (ref "S1")
      (value "SS12SDP2")
      (footprint "SS12SDP2")
      (description "Switch")
      (fields (field (name "MOUSER PART NUMBER") "633-SS12SDP2"))
      (libsource (lib "*") (part "SS12SDP2"))
    )
    (comp (ref "TP5")
      (value "TP")
      (footprint "TP1")
      (description "Test Point")
      (libsource (lib "VioletofSun") (part "TP1"))
    )
    (comp (ref "TP6")
      (value "TP")
      (footprint "TP1")
      (description "Test Point")
      (libsource (lib "") (part "TP1_1"))
    )
    (comp (ref "TP7")
      (value "TP")
      (footprint "TP1")
      (description "Test Point")
      (libsource (lib "VioletofSun") (part "TP1"))
    )
    (comp (ref "TP8")
      (value "TP")
      (footprint "TP1")
      (description "Test Point")
      (libsource (lib "") (part "TP1_1"))
    )
    (comp (ref "TP9")
      (value "TP")
      (footprint "TP1")
      (description "Test Point")
      (libsource (lib "VioletofSun") (part "TP1"))
    )
    (comp (ref "TP10")
      (value "TP")
      (footprint "TP1")
      (description "Test Point")
      (libsource (lib "VioletofSun") (part "TP1"))
    )
    (comp (ref "U1")
      (value "MCP73832T-2ACI/OT")
      (footprint "SOT-23-OT5_N")
      (fields (field (name "PUBLISHER") "Altium Limited"))
      (libsource (lib "Microchip Power Mgt Battery Management") (part "MCP73832T-2ACI/OT"))
    )
    (comp (ref "U2")
      (value "Part Number: ADS1299IPAGR")
      (footprint "QFP50P1200X1200X120-64N")
      (description "No Description Available")
      (fields
        (field (name "MANUFACTURER_PART_NUMBER") "ADS1299IPAGR")
        (field (name "COPYRIGHT") "Copyright (C) 2018 Accelerated Designs. All rights reserved")
      )
      (libsource (lib "Flex-PCB-fmECG") (part "ADS1299IPAGR"))
    )
    (comp (ref "U3")
      (value "OPA2376AIDR")
      (footprint "D8")
      (description "No Description Available")
      (fields (field (name "COPYRIGHT") "Copyright (C) 2018 Accelerated Designs. All rights reserved"))
      (libsource (lib "2019-06-26_00-32-27") (part "OPA2376AIDR"))
    )
    (comp (ref "U4")
      (value "Part Number: TPS63060DSCR")
      (footprint "DSC10_1P70X2P15")
      (description "No Description Available")
      (fields
        (field (name "MANUFACTURER_PART_NUMBER") "TPS63060DSCR")
        (field (name "MANUFACTURER") "Texas Instruments")
        (field (name "COPYRIGHT") "Copyright (C) 2018 Accelerated Designs. All rights reserved")
      )
      (libsource (lib "2019-06-25_17-28-37") (part "TPS63060DSCR"))
    )
    (comp (ref "U6")
      (value "LMC6442")
      (footprint "SOIC127P599X175-8N")
      (description "10V, 0.1V/?C, High-Precision, Low-Power Operational Amplifier 8-SOIC")
      (fields (field (name "MF") "Texas Instruments") (field (name "MP") "OPA2277U"))
      (libsource (lib "OPA2277U") (part "OPA2277U"))
    )
    (comp (ref "U7")
      (value "LMC6442")
      (footprint "SOIC127P599X175-8N")
      (description "10V, 0.1V/?C, High-Precision, Low-Power Operational Amplifier 8-SOIC")
      (fields (field (name "MF") "Texas Instruments") (field (name "MP") "OPA2277U"))
      (libsource (lib "OPA2277U") (part "OPA2277U"))
    )
    (comp (ref "U8")
      (value "LMC6442")
      (footprint "SOIC127P599X175-8N")
      (description "10V, 0.1V/?C, High-Precision, Low-Power Operational Amplifier 8-SOIC")
      (fields (field (name "MF") "Texas Instruments") (field (name "MP") "OPA2277U"))
      (libsource (lib "Flex-PCB-fmECG") (part "OPA2277U"))
    )
    (comp (ref "U9")
      (value "LMC6442")
      (footprint "SOIC127P599X175-8N")
      (description "10V, 0.1V/?C, High-Precision, Low-Power Operational Amplifier 8-SOIC")
      (fields (field (name "MF") "Texas Instruments") (field (name "MP") "OPA2277U"))
      (libsource (lib "Flex-PCB-fmECG") (part "OPA2277U"))
    )
    (comp (ref "X1")
      (value "32.768kHz")
      (footprint "Crystal 32.768kHz SMD")
      (description "Crystal For all Crystal 2pin.")
      (libsource (lib "mylib") (part "Crystal"))
    )
  )
  (nets
    (net (code "1") (name "/+2.5V") (class "Default")
      (node (ref "C1") (pin "2") (pinfunction "2_2") (pintype "passive"))
      (node (ref "C12") (pin "1") (pinfunction "1_1") (pintype "passive"))
      (node (ref "C26") (pin "2") (pinfunction "2_2") (pintype "passive"))
      (node (ref "C27") (pin "2") (pinfunction "2_2") (pintype "passive"))
      (node (ref "C3") (pin "2") (pinfunction "2_2") (pintype "passive"))
      (node (ref "C32") (pin "2") (pinfunction "2_2") (pintype "passive"))
      (node (ref "C33") (pin "2") (pinfunction "2_2") (pintype "passive"))
      (node (ref "C34") (pin "2") (pinfunction "2_2") (pintype "passive"))
      (node (ref "C35") (pin "2") (pinfunction "2_2") (pintype "passive"))
      (node (ref "C49") (pin "2") (pinfunction "2_2") (pintype "passive"))
      (node (ref "C50") (pin "2") (pinfunction "2_2") (pintype "passive"))
      (node (ref "C57") (pin "2") (pinfunction "2_2") (pintype "passive"))
      (node (ref "C61") (pin "2") (pinfunction "2_2") (pintype "passive"))
      (node (ref "C65") (pin "2") (pinfunction "2_2") (pintype "passive"))
      (node (ref "C66") (pin "2") (pinfunction "2_2") (pintype "passive"))
      (node (ref "C73") (pin "2") (pinfunction "2_2") (pintype "passive"))
      (node (ref "C75") (pin "2") (pinfunction "2_2") (pintype "passive"))
      (node (ref "J12") (pin "4") (pinfunction "4_4") (pintype "passive"))
      (node (ref "J13") (pin "4") (pinfunction "4_4") (pintype "passive"))
      (node (ref "J14") (pin "12") (pinfunction "12_12") (pintype "passive"))
      (node (ref "J14") (pin "14") (pinfunction "14_14") (pintype "passive"))
      (node (ref "J14") (pin "20") (pinfunction "20_20") (pintype "passive"))
      (node (ref "J14") (pin "6") (pinfunction "6_6") (pintype "passive"))
      (node (ref "J5") (pin "4") (pinfunction "4_4") (pintype "passive"))
      (node (ref "J9") (pin "4") (pinfunction "4_4") (pintype "passive"))
      (node (ref "L5") (pin "2") (pinfunction "2_2") (pintype "passive"))
      (node (ref "Pad1") (pin "1") (pinfunction "1_1") (pintype "passive"))
      (node (ref "Pad2") (pin "4") (pinfunction "4_4") (pintype "passive"))
      (node (ref "Pad3") (pin "1") (pinfunction "1_1") (pintype "passive"))
      (node (ref "Pad4") (pin "4") (pinfunction "4_4") (pintype "passive"))
      (node (ref "TP10") (pin "1") (pinfunction "1_1") (pintype "passive"))
      (node (ref "TP5") (pin "1") (pinfunction "1_1") (pintype "passive"))
      (node (ref "U2") (pin "17") (pinfunction "SRB1_17") (pintype "bidirectional"))
      (node (ref "U2") (pin "19") (pinfunction "AVDD_19") (pintype "power_in"))
      (node (ref "U2") (pin "21") (pinfunction "AVDD_21") (pintype "power_in"))
      (node (ref "U2") (pin "22") (pinfunction "AVDD_22") (pintype "power_in"))
      (node (ref "U2") (pin "54") (pinfunction "AVDD1_54") (pintype "power_in"))
      (node (ref "U2") (pin "56") (pinfunction "AVDD_56") (pintype "power_in"))
      (node (ref "U2") (pin "59") (pinfunction "AVDD_59") (pintype "power_in"))
      (node (ref "U3") (pin "6") (pinfunction "INB-_6") (pintype "input"))
      (node (ref "U3") (pin "7") (pinfunction "OUTB_7") (pintype "output"))
      (node (ref "U3") (pin "8") (pinfunction "V+_8") (pintype "power_in"))
      (node (ref "U6") (pin "8") (pinfunction "V+_8") (pintype "power_in"))
      (node (ref "U7") (pin "8") (pinfunction "V+_8") (pintype "power_in"))
      (node (ref "U8") (pin "8") (pinfunction "V+_8") (pintype "power_in"))
      (node (ref "U9") (pin "8") (pinfunction "V+_8") (pintype "power_in"))
    )
    (net (code "2") (name "/+IN_A5") (class "Default")
      (node (ref "C55") (pin "2") (pinfunction "2_2") (pintype "passive"))
      (node (ref "Cn_5") (pin "2") (pinfunction "2_2") (pintype "passive"))
      (node (ref "D1_5") (pin "1") (pinfunction "A_1") (pintype "passive"))
      (node (ref "D2_5") (pin "3") (pinfunction "K_3") (pintype "passive"))
      (node (ref "J4") (pin "3") (pinfunction "3_3") (pintype "passive"))
      (node (ref "U6") (pin "3") (pinfunction "+IN_A_3") (pintype "input"))
    )
    (net (code "3") (name "/+IN_A6") (class "Default")
      (node (ref "C59") (pin "1") (pinfunction "1_1") (pintype "passive"))
      (node (ref "Cn") (pin "2") (pinfunction "2_2") (pintype "passive"))
      (node (ref "D1_6") (pin "1") (pinfunction "A_1") (pintype "passive"))
      (node (ref "D2_6") (pin "3") (pinfunction "K_3") (pintype "passive"))
      (node (ref "J10") (pin "3") (pinfunction "3_3") (pintype "passive"))
      (node (ref "U7") (pin "3") (pinfunction "+IN_A_3") (pintype "input"))
    )
    (net (code "4") (name "/+IN_B3") (class "Default")
      (node (ref "C3_3") (pin "1") (pinfunction "1_1") (pintype "passive"))
      (node (ref "J13") (pin "1") (pinfunction "1_1") (pintype "passive"))
      (node (ref "R3_3") (pin "2") (pinfunction "2_2") (pintype "passive"))
      (node (ref "U9") (pin "5") (pinfunction "+IN_B_5") (pintype "input"))
    )
    (net (code "5") (name "/+IN_B4") (class "Default")
      (node (ref "C3_4") (pin "1") (pinfunction "1_1") (pintype "passive"))
      (node (ref "J9") (pin "1") (pinfunction "1_1") (pintype "passive"))
      (node (ref "R3_4") (pin "2") (pinfunction "2_2") (pintype "passive"))
      (node (ref "U8") (pin "5") (pinfunction "+IN_B_5") (pintype "input"))
    )
    (net (code "6") (name "/+IN_B5") (class "Default")
      (node (ref "C56") (pin "1") (pinfunction "1_1") (pintype "passive"))
      (node (ref "J5") (pin "1") (pinfunction "1_1") (pintype "passive"))
      (node (ref "R23") (pin "2") (pinfunction "2_2") (pintype "passive"))
      (node (ref "U6") (pin "5") (pinfunction "+IN_B_5") (pintype "input"))
    )
    (net (code "7") (name "/+IN_B6") (class "Default")
      (node (ref "C60") (pin "1") (pinfunction "1_1") (pintype "passive"))
      (node (ref "J12") (pin "1") (pinfunction "1_1") (pintype "passive"))
      (node (ref "R25") (pin "2") (pinfunction "2_2") (pintype "passive"))
      (node (ref "U7") (pin "5") (pinfunction "+IN_B_5") (pintype "input"))
    )
    (net (code "8") (name "/-2.5V") (class "Default")
      (node (ref "C13") (pin "2") (pinfunction "2_2") (pintype "passive"))
      (node (ref "C2") (pin "2") (pinfunction "2_2") (pintype "passive"))
      (node (ref "C20") (pin "2") (pinfunction "2_2") (pintype "passive"))
      (node (ref "C21") (pin "1") (pinfunction "1_1") (pintype "passive"))
      (node (ref "C22") (pin "2") (pinfunction "2_2") (pintype "passive"))
      (node (ref "C23") (pin "1") (pinfunction "1_1") (pintype "passive"))
      (node (ref "C24") (pin "1") (pinfunction "1_1") (pintype "passive"))
      (node (ref "C25") (pin "1") (pinfunction "1_1") (pintype "passive"))
      (node (ref "C26") (pin "1") (pinfunction "1_1") (pintype "passive"))
      (node (ref "C27") (pin "1") (pinfunction "1_1") (pintype "passive"))
      (node (ref "C28") (pin "2") (pinfunction "2_2") (pintype "passive"))
      (node (ref "C29") (pin "2") (pinfunction "2_2") (pintype "passive"))
      (node (ref "C32") (pin "1") (pinfunction "1_1") (pintype "passive"))
      (node (ref "C33") (pin "1") (pinfunction "1_1") (pintype "passive"))
      (node (ref "C4") (pin "2") (pinfunction "2_2") (pintype "passive"))
      (node (ref "C45") (pin "2") (pinfunction "2_2") (pintype "passive"))
      (node (ref "C58") (pin "2") (pinfunction "2_2") (pintype "passive"))
      (node (ref "C62") (pin "2") (pinfunction "2_2") (pintype "passive"))
      (node (ref "C69") (pin "2") (pinfunction "2_2") (pintype "passive"))
      (node (ref "C70") (pin "2") (pinfunction "2_2") (pintype "passive"))
      (node (ref "C74") (pin "2") (pinfunction "2_2") (pintype "passive"))
      (node (ref "C79") (pin "2") (pinfunction "2_2") (pintype "passive"))
      (node (ref "J10") (pin "4") (pinfunction "4_4") (pintype "passive"))
      (node (ref "J11") (pin "4") (pinfunction "4_4") (pintype "passive"))
      (node (ref "J14") (pin "10") (pinfunction "10_10") (pintype "passive"))
      (node (ref "J14") (pin "16") (pinfunction "16_16") (pintype "passive"))
      (node (ref "J14") (pin "18") (pinfunction "18_18") (pintype "passive"))
      (node (ref "J14") (pin "8") (pinfunction "8_8") (pintype "passive"))
      (node (ref "J3") (pin "4") (pinfunction "4_4") (pintype "passive"))
      (node (ref "J4") (pin "4") (pinfunction "4_4") (pintype "passive"))
      (node (ref "L2") (pin "2") (pinfunction "2_2") (pintype "passive"))
      (node (ref "Pad1") (pin "4") (pinfunction "4_4") (pintype "passive"))
      (node (ref "Pad2") (pin "1") (pinfunction "1_1") (pintype "passive"))
      (node (ref "Pad3") (pin "4") (pinfunction "4_4") (pintype "passive"))
      (node (ref "Pad4") (pin "1") (pinfunction "1_1") (pintype "passive"))
      (node (ref "TP9") (pin "1") (pinfunction "1_1") (pintype "passive"))
      (node (ref "U2") (pin "20") (pinfunction "AVSS_20") (pintype "power_in"))
      (node (ref "U2") (pin "23") (pinfunction "AVSS_23") (pintype "power_in"))
      (node (ref "U2") (pin "25") (pinfunction "VREFN_25") (pintype "input"))
      (node (ref "U2") (pin "32") (pinfunction "AVSS_32") (pintype "power_in"))
      (node (ref "U2") (pin "53") (pinfunction "AVSS1_53") (pintype "power_in"))
      (node (ref "U2") (pin "57") (pinfunction "AVSS_57") (pintype "power_in"))
      (node (ref "U2") (pin "58") (pinfunction "AVSS_58") (pintype "power_in"))
      (node (ref "U3") (pin "4") (pinfunction "V-_4") (pintype "power_in"))
      (node (ref "U6") (pin "4") (pinfunction "V-_4") (pintype "power_in"))
      (node (ref "U7") (pin "4") (pinfunction "V-_4") (pintype "power_in"))
      (node (ref "U8") (pin "4") (pinfunction "V-_4") (pintype "power_in"))
      (node (ref "U9") (pin "4") (pinfunction "V-_4") (pintype "power_in"))
    )
    (net (code "9") (name "/-IN_B5") (class "Default")
      (node (ref "C56") (pin "2") (pinfunction "2_2") (pintype "passive"))
      (node (ref "R1_5") (pin "1") (pinfunction "1_1") (pintype "passive"))
      (node (ref "R24") (pin "2") (pinfunction "2_2") (pintype "passive"))
      (node (ref "R2_5") (pin "2") (pinfunction "2_2") (pintype "passive"))
      (node (ref "Rc_5") (pin "1") (pinfunction "1_1") (pintype "passive"))
      (node (ref "U6") (pin "2") (pinfunction "-IN_A_2") (pintype "input"))
    )
    (net (code "10") (name "/-IN_B6") (class "Default")
      (node (ref "C60") (pin "2") (pinfunction "2_2") (pintype "passive"))
      (node (ref "R1_6") (pin "1") (pinfunction "1_1") (pintype "passive"))
      (node (ref "R26") (pin "2") (pinfunction "2_2") (pintype "passive"))
      (node (ref "R2_6") (pin "2") (pinfunction "2_2") (pintype "passive"))
      (node (ref "Rc_6") (pin "1") (pinfunction "1_1") (pintype "passive"))
      (node (ref "U7") (pin "2") (pinfunction "-IN_A_2") (pintype "input"))
    )
    (net (code "11") (name "/BIAS") (class "Default")
      (node (ref "C14") (pin "2") (pinfunction "2_2") (pintype "passive"))
      (node (ref "R17") (pin "2") (pinfunction "2_2") (pintype "passive"))
      (node (ref "TP8") (pin "1") (pinfunction "1_1") (pintype "passive"))
      (node (ref "U2") (pin "62") (pinfunction "BIASIN_62") (pintype "input"))
      (node (ref "U2") (pin "63") (pinfunction "BIASOUT_63") (pintype "output"))
      (node (ref "U3") (pin "3") (pinfunction "INA+_3") (pintype "input"))
    )
    (net (code "12") (name "/CS") (class "Default")
      (node (ref "J2") (pin "1") (pinfunction "1_1") (pintype "passive"))
      (node (ref "M1") (pin "25") (pinfunction "P0.11_25") (pintype "passive"))
      (node (ref "R20") (pin "1") (pinfunction "1_1") (pintype "passive"))
      (node (ref "U2") (pin "39") (pinfunction "*CS_39") (pintype "input"))
    )
    (net (code "13") (name "/CS_1") (class "Default")
      (node (ref "J7") (pin "2") (pinfunction "CD/DAT3_2") (pintype "bidirectional"))
      (node (ref "M1") (pin "17") (pinfunction "P0.04_17") (pintype "passive"))
    )
    (net (code "14") (name "/DRDY") (class "Default")
      (node (ref "J1") (pin "2") (pinfunction "2_2") (pintype "passive"))
      (node (ref "M1") (pin "30") (pinfunction "P0.16_30") (pintype "passive"))
      (node (ref "U2") (pin "47") (pinfunction "*DRDY_47") (pintype "output"))
    )
    (net (code "15") (name "/DVDD") (class "Default")
      (node (ref "C15") (pin "2") (pinfunction "2_2") (pintype "passive"))
      (node (ref "C16") (pin "2") (pinfunction "2_2") (pintype "passive"))
      (node (ref "C30") (pin "2") (pinfunction "2_2") (pintype "passive"))
      (node (ref "C31") (pin "2") (pinfunction "2_2") (pintype "passive"))
      (node (ref "C39") (pin "2") (pinfunction "2_2") (pintype "passive"))
      (node (ref "C40") (pin "2") (pinfunction "2_2") (pintype "passive"))
      (node (ref "C46") (pin "2") (pinfunction "2_2") (pintype "passive"))
      (node (ref "C47") (pin "2") (pinfunction "2_2") (pintype "passive"))
      (node (ref "IC2") (pin "8") (pinfunction "V+_8") (pintype "passive"))
      (node (ref "IC4") (pin "1") (pinfunction "IN_1") (pintype "input"))
      (node (ref "IC4") (pin "3") (pinfunction "EN_3") (pintype "passive"))
      (node (ref "J7") (pin "4") (pinfunction "VDD_4") (pintype "power_in"))
      (node (ref "J8") (pin "1") (pinfunction "1_1") (pintype "passive"))
      (node (ref "M1") (pin "11") (pinfunction "VDD_11") (pintype "passive"))
      (node (ref "R15") (pin "2") (pinfunction "2_2") (pintype "passive"))
      (node (ref "R16") (pin "2") (pinfunction "2_2") (pintype "passive"))
      (node (ref "R19") (pin "2") (pinfunction "2_2") (pintype "passive"))
      (node (ref "R20") (pin "2") (pinfunction "2_2") (pintype "passive"))
      (node (ref "TP7") (pin "1") (pinfunction "1_1") (pintype "passive"))
      (node (ref "U2") (pin "48") (pinfunction "DVDD_48") (pintype "power_in"))
      (node (ref "U2") (pin "50") (pinfunction "DVDD_50") (pintype "power_in"))
      (node (ref "U2") (pin "52") (pinfunction "CLKSEL_52") (pintype "input"))
      (node (ref "U4") (pin "9") (pinfunction "VOUT_9") (pintype "output"))
    )
    (net (code "16") (name "/Elec_1") (class "Default")
      (node (ref "C5") (pin "2") (pinfunction "2_2") (pintype "passive"))
      (node (ref "R5") (pin "2") (pinfunction "2_2") (pintype "passive"))
      (node (ref "U2") (pin "14") (pinfunction "IN2P_14") (pintype "input"))
    )
    (net (code "17") (name "/Elec_2") (class "Default")
      (node (ref "C6") (pin "2") (pinfunction "2_2") (pintype "passive"))
      (node (ref "R6") (pin "2") (pinfunction "2_2") (pintype "passive"))
      (node (ref "U2") (pin "13") (pinfunction "IN2N_13") (pintype "input"))
    )
    (net (code "18") (name "/Elec_3") (class "Default")
      (node (ref "C7") (pin "2") (pinfunction "2_2") (pintype "passive"))
      (node (ref "J14") (pin "7") (pinfunction "7_7") (pintype "passive"))
      (node (ref "Pad1") (pin "3") (pinfunction "3_3") (pintype "passive"))
      (node (ref "R7") (pin "2") (pinfunction "2_2") (pintype "passive"))
      (node (ref "U2") (pin "12") (pinfunction "IN3P_12") (pintype "input"))
    )
    (net (code "19") (name "/Elec_4") (class "Default")
      (node (ref "C8") (pin "2") (pinfunction "2_2") (pintype "passive"))
      (node (ref "J14") (pin "9") (pinfunction "9_9") (pintype "passive"))
      (node (ref "Pad2") (pin "2") (pinfunction "2_2") (pintype "passive"))
      (node (ref "R8") (pin "2") (pinfunction "2_2") (pintype "passive"))
      (node (ref "U2") (pin "11") (pinfunction "IN3N_11") (pintype "input"))
    )
    (net (code "20") (name "/Elec_5") (class "Default")
      (node (ref "C63") (pin "2") (pinfunction "2_2") (pintype "passive"))
      (node (ref "J14") (pin "15") (pinfunction "15_15") (pintype "passive"))
      (node (ref "Pad3") (pin "3") (pinfunction "3_3") (pintype "passive"))
      (node (ref "R27") (pin "2") (pinfunction "2_2") (pintype "passive"))
      (node (ref "U2") (pin "10") (pinfunction "IN4P_10") (pintype "input"))
    )
    (net (code "21") (name "/Elec_6") (class "Default")
      (node (ref "C64") (pin "2") (pinfunction "2_2") (pintype "passive"))
      (node (ref "J14") (pin "17") (pinfunction "17_17") (pintype "passive"))
      (node (ref "Pad4") (pin "2") (pinfunction "2_2") (pintype "passive"))
      (node (ref "R28") (pin "2") (pinfunction "2_2") (pintype "passive"))
      (node (ref "U2") (pin "9") (pinfunction "IN4N_9") (pintype "input"))
    )
    (net (code "22") (name "/Elec_7") (class "Default")
      (node (ref "C52") (pin "2") (pinfunction "2_2") (pintype "passive"))
      (node (ref "R3") (pin "1") (pinfunction "1_1") (pintype "passive"))
      (node (ref "U2") (pin "16") (pinfunction "IN1P_16") (pintype "input"))
    )
    (net (code "23") (name "/Elec_8") (class "Default")
      (node (ref "C67") (pin "2") (pinfunction "2_2") (pintype "passive"))
      (node (ref "R4") (pin "1") (pinfunction "1_1") (pintype "passive"))
      (node (ref "U2") (pin "15") (pinfunction "IN1N_15") (pintype "input"))
    )
    (net (code "24") (name "/GUARD_3") (class "Default")
      (node (ref "J11") (pin "2") (pinfunction "2_2") (pintype "passive"))
      (node (ref "R1_3") (pin "1") (pinfunction "1_1") (pintype "passive"))
      (node (ref "R2_3") (pin "2") (pinfunction "2_2") (pintype "passive"))
      (node (ref "Rc_3") (pin "1") (pinfunction "1_1") (pintype "passive"))
      (node (ref "U9") (pin "2") (pinfunction "-IN_A_2") (pintype "input"))
    )
    (net (code "25") (name "/GUARD_4") (class "Default")
      (node (ref "J3") (pin "2") (pinfunction "2_2") (pintype "passive"))
      (node (ref "R1_4") (pin "1") (pinfunction "1_1") (pintype "passive"))
      (node (ref "R2_4") (pin "2") (pinfunction "2_2") (pintype "passive"))
      (node (ref "Rc_4") (pin "1") (pinfunction "1_1") (pintype "passive"))
      (node (ref "U8") (pin "2") (pinfunction "-IN_A_2") (pintype "input"))
    )
    (net (code "26") (name "/GUARD_5") (class "Default")
      (node (ref "R24") (pin "1") (pinfunction "1_1") (pintype "passive"))
    )
    (net (code "27") (name "/GUARD_6") (class "Default")
      (node (ref "R26") (pin "1") (pinfunction "1_1") (pintype "passive"))
    )
    (net (code "28") (name "/MISO") (class "Default")
      (node (ref "J2") (pin "3") (pinfunction "3_3") (pintype "passive"))
      (node (ref "J7") (pin "7") (pinfunction "DAT0_7") (pintype "bidirectional"))
      (node (ref "M1") (pin "26") (pinfunction "P0.12_26") (pintype "passive"))
      (node (ref "U2") (pin "43") (pinfunction "DOUT_43") (pintype "output"))
    )
    (net (code "29") (name "/MOSI") (class "Default")
      (node (ref "J2") (pin "4") (pinfunction "4_4") (pintype "passive"))
      (node (ref "J7") (pin "3") (pinfunction "CMD_3") (pintype "bidirectional"))
      (node (ref "M1") (pin "27") (pinfunction "P0.13_27") (pintype "passive"))
      (node (ref "U2") (pin "34") (pinfunction "DIN_34") (pintype "input"))
    )
    (net (code "30") (name "/OUT_A3") (class "Default")
      (node (ref "C3_3") (pin "2") (pinfunction "2_2") (pintype "passive"))
      (node (ref "J11") (pin "1") (pinfunction "1_1") (pintype "passive"))
      (node (ref "R1_3") (pin "2") (pinfunction "2_2") (pintype "passive"))
      (node (ref "Rn1_3") (pin "2") (pinfunction "2_2") (pintype "passive"))
      (node (ref "Rn_3") (pin "1") (pinfunction "1_1") (pintype "passive"))
      (node (ref "U9") (pin "1") (pinfunction "OUT_A_1") (pintype "output"))
    )
    (net (code "31") (name "/OUT_A4") (class "Default")
      (node (ref "C3_4") (pin "2") (pinfunction "2_2") (pintype "passive"))
      (node (ref "J3") (pin "1") (pinfunction "1_1") (pintype "passive"))
      (node (ref "R1_4") (pin "2") (pinfunction "2_2") (pintype "passive"))
      (node (ref "Rn1_4") (pin "2") (pinfunction "2_2") (pintype "passive"))
      (node (ref "Rn_4") (pin "1") (pinfunction "1_1") (pintype "passive"))
      (node (ref "U8") (pin "1") (pinfunction "OUT_A_1") (pintype "output"))
    )
    (net (code "32") (name "/OUT_A5") (class "Default")
      (node (ref "J4") (pin "1") (pinfunction "1_1") (pintype "passive"))
      (node (ref "J4") (pin "2") (pinfunction "2_2") (pintype "passive"))
      (node (ref "R1_5") (pin "2") (pinfunction "2_2") (pintype "passive"))
      (node (ref "Rn1_5") (pin "2") (pinfunction "2_2") (pintype "passive"))
      (node (ref "U6") (pin "1") (pinfunction "OUT_A_1") (pintype "output"))
    )
    (net (code "33") (name "/OUT_A6") (class "Default")
      (node (ref "J10") (pin "1") (pinfunction "1_1") (pintype "passive"))
      (node (ref "J10") (pin "2") (pinfunction "2_2") (pintype "passive"))
      (node (ref "R1_6") (pin "2") (pinfunction "2_2") (pintype "passive"))
      (node (ref "Rn1") (pin "2") (pinfunction "2_2") (pintype "passive"))
      (node (ref "U7") (pin "1") (pinfunction "OUT_A_1") (pintype "output"))
    )
    (net (code "34") (name "/PWDN") (class "Default")
      (node (ref "J1") (pin "4") (pinfunction "4_4") (pintype "passive"))
      (node (ref "M1") (pin "34") (pinfunction "P0.20_34") (pintype "passive"))
      (node (ref "R19") (pin "1") (pinfunction "1_1") (pintype "passive"))
      (node (ref "U2") (pin "35") (pinfunction "*PWDN_35") (pintype "power_in"))
    )
    (net (code "35") (name "/REF_IN") (class "Default")
      (node (ref "TP6") (pin "1") (pinfunction "1_1") (pintype "passive"))
      (node (ref "U3") (pin "5") (pinfunction "INB+_5") (pintype "input"))
    )
    (net (code "36") (name "/RESET") (class "Default")
      (node (ref "J1") (pin "3") (pinfunction "3_3") (pintype "passive"))
      (node (ref "M1") (pin "29") (pinfunction "P0.15_29") (pintype "passive"))
      (node (ref "U2") (pin "36") (pinfunction "*RESET_36") (pintype "input"))
    )
    (net (code "37") (name "/SCK") (class "Default")
      (node (ref "J2") (pin "2") (pinfunction "2_2") (pintype "passive"))
      (node (ref "M1") (pin "28") (pinfunction "P0.14_28") (pintype "passive"))
      (node (ref "U2") (pin "40") (pinfunction "SCLK_40") (pintype "input"))
    )
    (net (code "38") (name "/START") (class "Default")
      (node (ref "J1") (pin "1") (pinfunction "1_1") (pintype "passive"))
      (node (ref "M1") (pin "38") (pinfunction "P0.22_38") (pintype "passive"))
      (node (ref "U2") (pin "38") (pinfunction "START_38") (pintype "input"))
    )
    (net (code "39") (name "/SWDIO") (class "Default")
      (node (ref "J8") (pin "2") (pinfunction "2_2") (pintype "passive"))
      (node (ref "M1") (pin "37") (pinfunction "SWDIO_37") (pintype "passive"))
    )
    (net (code "40") (name "/SWD_CLK") (class "Default")
      (node (ref "J7") (pin "5") (pinfunction "CLK_5") (pintype "input"))
      (node (ref "J8") (pin "3") (pinfunction "3_3") (pintype "passive"))
      (node (ref "M1") (pin "36") (pinfunction "SWDCLK_36") (pintype "passive"))
    )
    (net (code "41") (name "/Signal_1") (class "Default")
      (node (ref "J14") (pin "1") (pinfunction "1_1") (pintype "passive"))
      (node (ref "R5") (pin "1") (pinfunction "1_1") (pintype "passive"))
    )
    (net (code "42") (name "/Signal_2") (class "Default")
      (node (ref "J14") (pin "3") (pinfunction "3_3") (pintype "passive"))
      (node (ref "R6") (pin "1") (pinfunction "1_1") (pintype "passive"))
    )
    (net (code "43") (name "/Signal_3") (class "Default")
      (node (ref "C_test3") (pin "1") (pinfunction "1_1") (pintype "passive"))
      (node (ref "Cn_3") (pin "2") (pinfunction "2_2") (pintype "passive"))
      (node (ref "Cn_3a") (pin "1") (pinfunction "1_1") (pintype "passive"))
      (node (ref "D1_3") (pin "1") (pinfunction "A_1") (pintype "passive"))
      (node (ref "D2_3") (pin "3") (pinfunction "K_3") (pintype "passive"))
      (node (ref "J11") (pin "3") (pinfunction "3_3") (pintype "passive"))
      (node (ref "U9") (pin "3") (pinfunction "+IN_A_3") (pintype "input"))
    )
    (net (code "44") (name "/Signal_3_1") (class "Default")
      (node (ref "J13") (pin "2") (pinfunction "2_2") (pintype "passive"))
      (node (ref "J13") (pin "3") (pinfunction "3_3") (pintype "passive"))
      (node (ref "R7") (pin "1") (pinfunction "1_1") (pintype "passive"))
      (node (ref "U9") (pin "6") (pinfunction "-IN_B_6") (pintype "input"))
      (node (ref "U9") (pin "7") (pinfunction "OUT_B_7") (pintype "output"))
    )
    (net (code "45") (name "/Signal_4") (class "Default")
      (node (ref "C_test4") (pin "1") (pinfunction "1_1") (pintype "passive"))
      (node (ref "Cn_4") (pin "2") (pinfunction "2_2") (pintype "passive"))
      (node (ref "Cn_4a") (pin "1") (pinfunction "1_1") (pintype "passive"))
      (node (ref "D1_4") (pin "1") (pinfunction "A_1") (pintype "passive"))
      (node (ref "D2_4") (pin "3") (pinfunction "K_3") (pintype "passive"))
      (node (ref "J3") (pin "3") (pinfunction "3_3") (pintype "passive"))
      (node (ref "U8") (pin "3") (pinfunction "+IN_A_3") (pintype "input"))
    )
    (net (code "46") (name "/Signal_4_1") (class "Default")
      (node (ref "J9") (pin "2") (pinfunction "2_2") (pintype "passive"))
      (node (ref "J9") (pin "3") (pinfunction "3_3") (pintype "passive"))
      (node (ref "R8") (pin "1") (pinfunction "1_1") (pintype "passive"))
      (node (ref "U8") (pin "6") (pinfunction "-IN_B_6") (pintype "input"))
      (node (ref "U8") (pin "7") (pinfunction "OUT_B_7") (pintype "output"))
    )
    (net (code "47") (name "/Signal_5") (class "Default")
      (node (ref "C55") (pin "1") (pinfunction "1_1") (pintype "passive"))
      (node (ref "C_test5") (pin "2") (pinfunction "2_2") (pintype "passive"))
    )
    (net (code "48") (name "/Signal_5_1") (class "Default")
      (node (ref "J5") (pin "2") (pinfunction "2_2") (pintype "passive"))
      (node (ref "J5") (pin "3") (pinfunction "3_3") (pintype "passive"))
      (node (ref "R27") (pin "1") (pinfunction "1_1") (pintype "passive"))
      (node (ref "U6") (pin "6") (pinfunction "-IN_B_6") (pintype "input"))
      (node (ref "U6") (pin "7") (pinfunction "OUT_B_7") (pintype "output"))
    )
    (net (code "49") (name "/Signal_6") (class "Default")
      (node (ref "C59") (pin "2") (pinfunction "2_2") (pintype "passive"))
      (node (ref "C_test6") (pin "2") (pinfunction "2_2") (pintype "passive"))
    )
    (net (code "50") (name "/Signal_6_1") (class "Default")
      (node (ref "J12") (pin "2") (pinfunction "2_2") (pintype "passive"))
      (node (ref "J12") (pin "3") (pinfunction "3_3") (pintype "passive"))
      (node (ref "R28") (pin "1") (pinfunction "1_1") (pintype "passive"))
      (node (ref "U7") (pin "6") (pinfunction "-IN_B_6") (pintype "input"))
      (node (ref "U7") (pin "7") (pinfunction "OUT_B_7") (pintype "output"))
    )
    (net (code "51") (name "/Signal_7") (class "Default")
      (node (ref "J14") (pin "2") (pinfunction "2_2") (pintype "passive"))
      (node (ref "R3") (pin "2") (pinfunction "2_2") (pintype "passive"))
    )
    (net (code "52") (name "/Signal_8") (class "Default")
      (node (ref "J14") (pin "4") (pinfunction "4_4") (pintype "passive"))
      (node (ref "R4") (pin "2") (pinfunction "2_2") (pintype "passive"))
    )
    (net (code "53") (name "/VCC") (class "Default")
      (node (ref "C17") (pin "2") (pinfunction "2_2") (pintype "passive"))
      (node (ref "S1") (pin "3") (pinfunction "ON_2_3") (pintype "passive"))
      (node (ref "U4") (pin "2") (pinfunction "VIN_2") (pintype "input"))
      (node (ref "U4") (pin "3") (pinfunction "EN_3") (pintype "input"))
    )
    (net (code "54") (name "GND") (class "Default")
      (node (ref "C1") (pin "1") (pinfunction "1_1") (pintype "passive"))
      (node (ref "C10") (pin "1") (pinfunction "1_1") (pintype "passive"))
      (node (ref "C11") (pin "1") (pinfunction "1_1") (pintype "passive"))
      (node (ref "C12") (pin "2") (pinfunction "2_2") (pintype "passive"))
      (node (ref "C13") (pin "1") (pinfunction "1_1") (pintype "passive"))
      (node (ref "C15") (pin "1") (pinfunction "1_1") (pintype "passive"))
      (node (ref "C16") (pin "1") (pinfunction "1_1") (pintype "passive"))
      (node (ref "C17") (pin "1") (pinfunction "1_1") (pintype "passive"))
      (node (ref "C18") (pin "1") (pinfunction "1_1") (pintype "passive"))
      (node (ref "C19") (pin "1") (pinfunction "1_1") (pintype "passive"))
      (node (ref "C1_3") (pin "2") (pinfunction "2_2") (pintype "passive"))
      (node (ref "C1_4") (pin "2") (pinfunction "2_2") (pintype "passive"))
      (node (ref "C1_5") (pin "2") (pinfunction "2_2") (pintype "passive"))
      (node (ref "C1_6") (pin "2") (pinfunction "2_2") (pintype "passive"))
      (node (ref "C2") (pin "1") (pinfunction "1_1") (pintype "passive"))
      (node (ref "C28") (pin "1") (pinfunction "1_1") (pintype "passive"))
      (node (ref "C29") (pin "1") (pinfunction "1_1") (pintype "passive"))
      (node (ref "C3") (pin "1") (pinfunction "1_1") (pintype "passive"))
      (node (ref "C30") (pin "1") (pinfunction "1_1") (pintype "passive"))
      (node (ref "C31") (pin "1") (pinfunction "1_1") (pintype "passive"))
      (node (ref "C34") (pin "1") (pinfunction "1_1") (pintype "passive"))
      (node (ref "C35") (pin "1") (pinfunction "1_1") (pintype "passive"))
      (node (ref "C37") (pin "2") (pinfunction "2_2") (pintype "passive"))
      (node (ref "C38") (pin "1") (pinfunction "1_1") (pintype "passive"))
      (node (ref "C39") (pin "1") (pinfunction "1_1") (pintype "passive"))
      (node (ref "C4") (pin "1") (pinfunction "1_1") (pintype "passive"))
      (node (ref "C40") (pin "1") (pinfunction "1_1") (pintype "passive"))
      (node (ref "C41") (pin "1") (pinfunction "1_1") (pintype "passive"))
      (node (ref "C42") (pin "1") (pinfunction "1_1") (pintype "passive"))
      (node (ref "C43") (pin "1") (pinfunction "1_1") (pintype "passive"))
      (node (ref "C44") (pin "1") (pinfunction "1_1") (pintype "passive"))
      (node (ref "C45") (pin "1") (pinfunction "1_1") (pintype "passive"))
      (node (ref "C46") (pin "1") (pinfunction "1_1") (pintype "passive"))
      (node (ref "C47") (pin "1") (pinfunction "1_1") (pintype "passive"))
      (node (ref "C48") (pin "1") (pinfunction "1_1") (pintype "passive"))
      (node (ref "C49") (pin "1") (pinfunction "1_1") (pintype "passive"))
      (node (ref "C5") (pin "1") (pinfunction "1_1") (pintype "passive"))
      (node (ref "C50") (pin "1") (pinfunction "1_1") (pintype "passive"))
      (node (ref "C51") (pin "1") (pinfunction "1_1") (pintype "passive"))
      (node (ref "C52") (pin "1") (pinfunction "1_1") (pintype "passive"))
      (node (ref "C53") (pin "1") (pinfunction "1_1") (pintype "passive"))
      (node (ref "C54") (pin "1") (pinfunction "1_1") (pintype "passive"))
      (node (ref "C57") (pin "1") (pinfunction "1_1") (pintype "passive"))
      (node (ref "C58") (pin "1") (pinfunction "1_1") (pintype "passive"))
      (node (ref "C6") (pin "1") (pinfunction "1_1") (pintype "passive"))
      (node (ref "C61") (pin "1") (pinfunction "1_1") (pintype "passive"))
      (node (ref "C62") (pin "1") (pinfunction "1_1") (pintype "passive"))
      (node (ref "C63") (pin "1") (pinfunction "1_1") (pintype "passive"))
      (node (ref "C64") (pin "1") (pinfunction "1_1") (pintype "passive"))
      (node (ref "C65") (pin "1") (pinfunction "1_1") (pintype "passive"))
      (node (ref "C66") (pin "1") (pinfunction "1_1") (pintype "passive"))
      (node (ref "C67") (pin "1") (pinfunction "1_1") (pintype "passive"))
      (node (ref "C69") (pin "1") (pinfunction "1_1") (pintype "passive"))
      (node (ref "C7") (pin "1") (pinfunction "1_1") (pintype "passive"))
      (node (ref "C70") (pin "1") (pinfunction "1_1") (pintype "passive"))
      (node (ref "C73") (pin "1") (pinfunction "1_1") (pintype "passive"))
      (node (ref "C74") (pin "1") (pinfunction "1_1") (pintype "passive"))
      (node (ref "C75") (pin "1") (pinfunction "1_1") (pintype "passive"))
      (node (ref "C79") (pin "1") (pinfunction "1_1") (pintype "passive"))
      (node (ref "C8") (pin "1") (pinfunction "1_1") (pintype "passive"))
      (node (ref "C9") (pin "1") (pinfunction "1_1") (pintype "passive"))
      (node (ref "H1") (pin "4") (pinfunction "ID_4") (pintype "passive"))
      (node (ref "H1") (pin "5") (pinfunction "GND_5") (pintype "passive"))
      (node (ref "IC2") (pin "3") (pinfunction "GND_3") (pintype "passive"))
      (node (ref "IC3") (pin "1") (pinfunction "GND_1") (pintype "passive"))
      (node (ref "IC4") (pin "2") (pinfunction "GND_2") (pintype "power_in"))
      (node (ref "J14") (pin "11") (pinfunction "11_11") (pintype "passive"))
      (node (ref "J14") (pin "13") (pinfunction "13_13") (pintype "passive"))
      (node (ref "J14") (pin "19") (pinfunction "19_19") (pintype "passive"))
      (node (ref "J14") (pin "5") (pinfunction "5_5") (pintype "passive"))
      (node (ref "J6") (pin "2") (pinfunction "2_2") (pintype "passive"))
      (node (ref "J7") (pin "6") (pinfunction "VSS_6") (pintype "power_in"))
      (node (ref "J7") (pin "DL") (pinfunction "DET_LEVEL_DL") (pintype "passive"))
      (node (ref "J7") (pin "DS") (pinfunction "DET_SWT_DS") (pintype "passive"))
      (node (ref "J8") (pin "4") (pinfunction "4_4") (pintype "passive"))
      (node (ref "LED2") (pin "K") (pinfunction "K_K") (pintype "passive"))
      (node (ref "LED3") (pin "K") (pinfunction "K_K") (pintype "passive"))
      (node (ref "M1") (pin "1") (pinfunction "GND_1") (pintype "passive"))
      (node (ref "M1") (pin "12") (pinfunction "GND_12") (pintype "passive"))
      (node (ref "M1") (pin "24") (pinfunction "GND_24") (pintype "passive"))
      (node (ref "M1") (pin "39") (pinfunction "GND_39") (pintype "passive"))
      (node (ref "Pad1") (pin "2") (pinfunction "2_2") (pintype "passive"))
      (node (ref "Pad2") (pin "3") (pinfunction "3_3") (pintype "passive"))
      (node (ref "Pad3") (pin "2") (pinfunction "2_2") (pintype "passive"))
      (node (ref "Pad4") (pin "3") (pinfunction "3_3") (pintype "passive"))
      (node (ref "R11") (pin "2") (pinfunction "2_2") (pintype "passive"))
      (node (ref "R12") (pin "2") (pinfunction "2_2") (pintype "passive"))
      (node (ref "R13") (pin "2") (pinfunction "2_2") (pintype "passive"))
      (node (ref "R14") (pin "2") (pinfunction "2_2") (pintype "passive"))
      (node (ref "R18") (pin "1") (pinfunction "1_1") (pintype "passive"))
      (node (ref "R2") (pin "1") (pinfunction "1_1") (pintype "passive"))
      (node (ref "R23") (pin "1") (pinfunction "1_1") (pintype "passive"))
      (node (ref "R25") (pin "1") (pinfunction "1_1") (pintype "passive"))
      (node (ref "R29") (pin "2") (pinfunction "2_2") (pintype "passive"))
      (node (ref "R3_3") (pin "1") (pinfunction "1_1") (pintype "passive"))
      (node (ref "R3_4") (pin "1") (pinfunction "1_1") (pintype "passive"))
      (node (ref "R9") (pin "2") (pinfunction "2_2") (pintype "passive"))
      (node (ref "Rb_3") (pin "1") (pinfunction "1_1") (pintype "passive"))
      (node (ref "Rb_4") (pin "1") (pinfunction "1_1") (pintype "passive"))
      (node (ref "Rb_5") (pin "1") (pinfunction "1_1") (pintype "passive"))
      (node (ref "Rb_6") (pin "1") (pinfunction "1_1") (pintype "passive"))
      (node (ref "Rn2") (pin "1") (pinfunction "1_1") (pintype "passive"))
      (node (ref "Rn2_3") (pin "1") (pinfunction "1_1") (pintype "passive"))
      (node (ref "Rn2_4") (pin "1") (pinfunction "1_1") (pintype "passive"))
      (node (ref "Rn2_5") (pin "1") (pinfunction "1_1") (pintype "passive"))
      (node (ref "Rn_3") (pin "3") (pinfunction "3_3") (pintype "passive"))
      (node (ref "Rn_4") (pin "3") (pinfunction "3_3") (pintype "passive"))
      (node (ref "U1") (pin "2") (pinfunction "VSS_2") (pintype "power_in"))
      (node (ref "U2") (pin "31") (pinfunction "RESV1_31") (pintype "input"))
      (node (ref "U2") (pin "33") (pinfunction "DGND_33") (pintype "power_in"))
      (node (ref "U2") (pin "41") (pinfunction "DAISY_IN_41") (pintype "input"))
      (node (ref "U2") (pin "49") (pinfunction "DGND_49") (pintype "power_in"))
      (node (ref "U2") (pin "51") (pinfunction "DGND_51") (pintype "power_in"))
      (node (ref "U4") (pin "11") (pinfunction "EPAD_11") (pintype "passive"))
      (node (ref "U4") (pin "4") (pinfunction "PS/SYNC_4") (pintype "input"))
      (node (ref "U4") (pin "7") (pinfunction "GND_7") (pintype "power_in"))
    )
    (net (code "55") (name "Net-(C1_3-Pad1)") (class "Default")
      (node (ref "C1_3") (pin "1") (pinfunction "1_1") (pintype "passive"))
      (node (ref "R2_3") (pin "1") (pinfunction "1_1") (pintype "passive"))
    )
    (net (code "56") (name "Net-(C1_4-Pad1)") (class "Default")
      (node (ref "C1_4") (pin "1") (pinfunction "1_1") (pintype "passive"))
      (node (ref "R2_4") (pin "1") (pinfunction "1_1") (pintype "passive"))
    )
    (net (code "57") (name "Net-(C1_5-Pad1)") (class "Default")
      (node (ref "C1_5") (pin "1") (pinfunction "1_1") (pintype "passive"))
      (node (ref "R2_5") (pin "1") (pinfunction "1_1") (pintype "passive"))
    )
    (net (code "58") (name "Net-(C1_6-Pad1)") (class "Default")
      (node (ref "C1_6") (pin "1") (pinfunction "1_1") (pintype "passive"))
      (node (ref "R2_6") (pin "1") (pinfunction "1_1") (pintype "passive"))
    )
    (net (code "59") (name "Net-(Cn-Pad1)") (class "Default")
      (node (ref "Cn") (pin "1") (pinfunction "1_1") (pintype "passive"))
      (node (ref "Rn1") (pin "1") (pinfunction "1_1") (pintype "passive"))
      (node (ref "Rn2") (pin "2") (pinfunction "2_2") (pintype "passive"))
    )
    (net (code "60") (name "Net-(Cn_3-Pad1)") (class "Default")
      (node (ref "Cn_3") (pin "1") (pinfunction "1_1") (pintype "passive"))
      (node (ref "Cn_3a") (pin "2") (pinfunction "2_2") (pintype "passive"))
      (node (ref "Rn1_3") (pin "1") (pinfunction "1_1") (pintype "passive"))
      (node (ref "Rn2_3") (pin "2") (pinfunction "2_2") (pintype "passive"))
      (node (ref "Rn_3") (pin "2") (pinfunction "2_2") (pintype "passive"))
    )
    (net (code "61") (name "Net-(Cn_4-Pad1)") (class "Default")
      (node (ref "Cn_4") (pin "1") (pinfunction "1_1") (pintype "passive"))
      (node (ref "Cn_4a") (pin "2") (pinfunction "2_2") (pintype "passive"))
      (node (ref "Rn1_4") (pin "1") (pinfunction "1_1") (pintype "passive"))
      (node (ref "Rn2_4") (pin "2") (pinfunction "2_2") (pintype "passive"))
      (node (ref "Rn_4") (pin "2") (pinfunction "2_2") (pintype "passive"))
    )
    (net (code "62") (name "Net-(Cn_5-Pad1)") (class "Default")
      (node (ref "Cn_5") (pin "1") (pinfunction "1_1") (pintype "passive"))
      (node (ref "Rn1_5") (pin "1") (pinfunction "1_1") (pintype "passive"))
      (node (ref "Rn2_5") (pin "2") (pinfunction "2_2") (pintype "passive"))
    )
    (net (code "63") (name "Net-(D1-A)") (class "Default")
      (node (ref "C11") (pin "2") (pinfunction "2_2") (pintype "passive"))
      (node (ref "D1") (pin "2") (pinfunction "A_2") (pintype "passive"))
      (node (ref "J6") (pin "1") (pinfunction "1_1") (pintype "passive"))
      (node (ref "U1") (pin "3") (pinfunction "VBAT_3") (pintype "power_in"))
    )
    (net (code "64") (name "Net-(D1-K)") (class "Default")
      (node (ref "D1") (pin "1") (pinfunction "K_1") (pintype "passive"))
      (node (ref "S1") (pin "2") (pinfunction "COM_2") (pintype "passive"))
    )
    (net (code "65") (name "Net-(D1_3-K)") (class "Default")
      (node (ref "D1_3") (pin "3") (pinfunction "K_3") (pintype "passive"))
      (node (ref "D2_3") (pin "1") (pinfunction "A_1") (pintype "passive"))
      (node (ref "Rb_3") (pin "2") (pinfunction "2_2") (pintype "passive"))
      (node (ref "Rc_3") (pin "2") (pinfunction "2_2") (pintype "passive"))
    )
    (net (code "66") (name "Net-(D1_4-K)") (class "Default")
      (node (ref "D1_4") (pin "3") (pinfunction "K_3") (pintype "passive"))
      (node (ref "D2_4") (pin "1") (pinfunction "A_1") (pintype "passive"))
      (node (ref "Rb_4") (pin "2") (pinfunction "2_2") (pintype "passive"))
      (node (ref "Rc_4") (pin "2") (pinfunction "2_2") (pintype "passive"))
    )
    (net (code "67") (name "Net-(D1_5-K)") (class "Default")
      (node (ref "D1_5") (pin "3") (pinfunction "K_3") (pintype "passive"))
      (node (ref "D2_5") (pin "1") (pinfunction "A_1") (pintype "passive"))
      (node (ref "Rb_5") (pin "2") (pinfunction "2_2") (pintype "passive"))
      (node (ref "Rc_5") (pin "2") (pinfunction "2_2") (pintype "passive"))
    )
    (net (code "68") (name "Net-(D1_6-K)") (class "Default")
      (node (ref "D1_6") (pin "3") (pinfunction "K_3") (pintype "passive"))
      (node (ref "D2_6") (pin "1") (pinfunction "A_1") (pintype "passive"))
      (node (ref "Rb_6") (pin "2") (pinfunction "2_2") (pintype "passive"))
      (node (ref "Rc_6") (pin "2") (pinfunction "2_2") (pintype "passive"))
    )
    (net (code "69") (name "Net-(D2-A)") (class "Default")
      (node (ref "D2") (pin "2") (pinfunction "A_2") (pintype "passive"))
      (node (ref "H1") (pin "1") (pinfunction "VCC_1") (pintype "passive"))
    )
    (net (code "70") (name "Net-(D2-K)") (class "Default")
      (node (ref "C10") (pin "2") (pinfunction "2_2") (pintype "passive"))
      (node (ref "C9") (pin "2") (pinfunction "2_2") (pintype "passive"))
      (node (ref "D2") (pin "1") (pinfunction "K_1") (pintype "passive"))
      (node (ref "LED1") (pin "1") (pinfunction "1_1") (pintype "passive"))
      (node (ref "U1") (pin "4") (pinfunction "VDD_4") (pintype "power_in"))
    )
    (net (code "71") (name "Net-(IC2-CAP+)") (class "Default")
      (node (ref "C36") (pin "1") (pinfunction "1_1") (pintype "passive"))
      (node (ref "IC2") (pin "2") (pinfunction "CAP+_2") (pintype "passive"))
    )
    (net (code "72") (name "Net-(IC2-CAP-)") (class "Default")
      (node (ref "C36") (pin "2") (pinfunction "2_2") (pintype "passive"))
      (node (ref "IC2") (pin "4") (pinfunction "CAP-_4") (pintype "passive"))
    )
    (net (code "73") (name "Net-(IC2-OUT)") (class "Default")
      (node (ref "C41") (pin "2") (pinfunction "2_2") (pintype "passive"))
      (node (ref "C42") (pin "2") (pinfunction "2_2") (pintype "passive"))
      (node (ref "IC2") (pin "5") (pinfunction "OUT_5") (pintype "passive"))
      (node (ref "IC3") (pin "2") (pinfunction "IN_2") (pintype "passive"))
      (node (ref "IC3") (pin "3") (pinfunction "EN_3") (pintype "passive"))
    )
    (net (code "74") (name "Net-(IC3-NR{slash}FB)") (class "Default")
      (node (ref "C37") (pin "1") (pinfunction "1_1") (pintype "passive"))
      (node (ref "IC3") (pin "4") (pinfunction "NR/FB_4") (pintype "passive"))
      (node (ref "R1") (pin "1") (pinfunction "1_1") (pintype "passive"))
      (node (ref "R2") (pin "2") (pinfunction "2_2") (pintype "passive"))
    )
    (net (code "75") (name "Net-(IC3-OUT)") (class "Default")
      (node (ref "C43") (pin "2") (pinfunction "2_2") (pintype "passive"))
      (node (ref "C44") (pin "2") (pinfunction "2_2") (pintype "passive"))
      (node (ref "IC3") (pin "5") (pinfunction "OUT_5") (pintype "passive"))
      (node (ref "L2") (pin "1") (pinfunction "1_1") (pintype "passive"))
      (node (ref "R1") (pin "2") (pinfunction "2_2") (pintype "passive"))
    )
    (net (code "76") (name "Net-(IC4-BYP)") (class "Default")
      (node (ref "C51") (pin "2") (pinfunction "2_2") (pintype "passive"))
      (node (ref "IC4") (pin "4") (pinfunction "BYP_4") (pintype "passive"))
    )
    (net (code "77") (name "Net-(IC4-OUT)") (class "Default")
      (node (ref "C48") (pin "2") (pinfunction "2_2") (pintype "passive"))
      (node (ref "IC4") (pin "5") (pinfunction "OUT_5") (pintype "output"))
      (node (ref "L5") (pin "1") (pinfunction "1_1") (pintype "passive"))
    )
    (net (code "78") (name "Net-(L3-Pad1)") (class "Default")
      (node (ref "L3") (pin "1") (pinfunction "1_1") (pintype "passive"))
      (node (ref "L4") (pin "2") (pinfunction "2_2") (pintype "passive"))
    )
    (net (code "79") (name "Net-(LED1-Pad2)") (class "Default")
      (node (ref "LED1") (pin "2") (pinfunction "2_2") (pintype "passive"))
      (node (ref "R10") (pin "1") (pinfunction "1_1") (pintype "passive"))
    )
    (net (code "80") (name "Net-(LED2-PadA)") (class "Default")
      (node (ref "LED2") (pin "A") (pinfunction "A_A") (pintype "passive"))
      (node (ref "R21") (pin "2") (pinfunction "2_2") (pintype "passive"))
    )
    (net (code "81") (name "Net-(LED3-PadA)") (class "Default")
      (node (ref "LED3") (pin "A") (pinfunction "A_A") (pintype "passive"))
      (node (ref "R22") (pin "2") (pinfunction "2_2") (pintype "passive"))
    )
    (net (code "82") (name "Net-(M1-DCC)") (class "Default")
      (node (ref "L4") (pin "1") (pinfunction "1_1") (pintype "passive"))
      (node (ref "M1") (pin "10") (pinfunction "DCC_10") (pintype "passive"))
    )
    (net (code "83") (name "Net-(M1-DEC4)") (class "Default")
      (node (ref "C38") (pin "2") (pinfunction "2_2") (pintype "passive"))
      (node (ref "L3") (pin "2") (pinfunction "2_2") (pintype "passive"))
      (node (ref "M1") (pin "9") (pinfunction "DEC4_9") (pintype "passive"))
    )
    (net (code "84") (name "Net-(M1-P0.00{slash}XL1)") (class "Default")
      (node (ref "C53") (pin "2") (pinfunction "2_2") (pintype "passive"))
      (node (ref "M1") (pin "13") (pinfunction "P0.00/XL1_13") (pintype "passive"))
      (node (ref "X1") (pin "2") (pinfunction "2_2") (pintype "passive"))
    )
    (net (code "85") (name "Net-(M1-P0.01{slash}XL2)") (class "Default")
      (node (ref "C54") (pin "2") (pinfunction "2_2") (pintype "passive"))
      (node (ref "M1") (pin "14") (pinfunction "P0.01/XL2_14") (pintype "passive"))
      (node (ref "X1") (pin "1") (pinfunction "1_1") (pintype "passive"))
    )
    (net (code "86") (name "Net-(M1-P0.17)") (class "Default")
      (node (ref "M1") (pin "31") (pinfunction "P0.17_31") (pintype "passive"))
      (node (ref "R22") (pin "1") (pinfunction "1_1") (pintype "passive"))
    )
    (net (code "87") (name "Net-(M1-P0.18)") (class "Default")
      (node (ref "M1") (pin "32") (pinfunction "P0.18_32") (pintype "passive"))
      (node (ref "R21") (pin "1") (pinfunction "1_1") (pintype "passive"))
    )
    (net (code "88") (name "Net-(U1-PROG)") (class "Default")
      (node (ref "R9") (pin "1") (pinfunction "1_1") (pintype "passive"))
      (node (ref "U1") (pin "5") (pinfunction "PROG_5") (pintype "passive"))
    )
    (net (code "89") (name "Net-(U1-STAT)") (class "Default")
      (node (ref "R10") (pin "2") (pinfunction "2_2") (pintype "passive"))
      (node (ref "U1") (pin "1") (pinfunction "STAT_1") (pintype "open_collector"))
    )
    (net (code "90") (name "Net-(U2-BIASINV)") (class "Default")
      (node (ref "C14") (pin "1") (pinfunction "1_1") (pintype "passive"))
      (node (ref "R17") (pin "1") (pinfunction "1_1") (pintype "passive"))
      (node (ref "U2") (pin "61") (pinfunction "BIASINV_61") (pintype "bidirectional"))
    )
    (net (code "91") (name "Net-(U2-BIASREF)") (class "Default")
      (node (ref "R29") (pin "1") (pinfunction "1_1") (pintype "passive"))
      (node (ref "U2") (pin "60") (pinfunction "BIASREF_60") (pintype "input"))
    )
    (net (code "92") (name "Net-(U2-GPIO1)") (class "Default")
      (node (ref "R14") (pin "1") (pinfunction "1_1") (pintype "passive"))
      (node (ref "U2") (pin "42") (pinfunction "GPIO1_42") (pintype "bidirectional"))
    )
    (net (code "93") (name "Net-(U2-GPIO2)") (class "Default")
      (node (ref "R13") (pin "1") (pinfunction "1_1") (pintype "passive"))
      (node (ref "U2") (pin "44") (pinfunction "GPIO2_44") (pintype "bidirectional"))
    )
    (net (code "94") (name "Net-(U2-GPIO3)") (class "Default")
      (node (ref "R12") (pin "1") (pinfunction "1_1") (pintype "passive"))
      (node (ref "U2") (pin "45") (pinfunction "GPIO3_45") (pintype "bidirectional"))
    )
    (net (code "95") (name "Net-(U2-GPIO4)") (class "Default")
      (node (ref "R11") (pin "1") (pinfunction "1_1") (pintype "passive"))
      (node (ref "U2") (pin "46") (pinfunction "GPIO4_46") (pintype "bidirectional"))
    )
    (net (code "96") (name "Net-(U2-VCAP1)") (class "Default")
      (node (ref "C22") (pin "1") (pinfunction "1_1") (pintype "passive"))
      (node (ref "U2") (pin "28") (pinfunction "VCAP1_28") (pintype "passive"))
    )
    (net (code "97") (name "Net-(U2-VCAP2)") (class "Default")
      (node (ref "C21") (pin "2") (pinfunction "2_2") (pintype "passive"))
      (node (ref "U2") (pin "30") (pinfunction "VCAP2_30") (pintype "passive"))
    )
    (net (code "98") (name "Net-(U2-VCAP3)") (class "Default")
      (node (ref "C24") (pin "2") (pinfunction "2_2") (pintype "passive"))
      (node (ref "C25") (pin "2") (pinfunction "2_2") (pintype "passive"))
      (node (ref "U2") (pin "55") (pinfunction "VCAP3_55") (pintype "passive"))
    )
    (net (code "99") (name "Net-(U2-VCAP4)") (class "Default")
      (node (ref "C23") (pin "2") (pinfunction "2_2") (pintype "passive"))
      (node (ref "U2") (pin "26") (pinfunction "VCAP4_26") (pintype "output"))
    )
    (net (code "100") (name "Net-(U2-VREFP)") (class "Default")
      (node (ref "C20") (pin "1") (pinfunction "1_1") (pintype "passive"))
      (node (ref "U2") (pin "24") (pinfunction "VREFP_24") (pintype "bidirectional"))
    )
    (net (code "101") (name "Net-(U3-INA-)") (class "Default")
      (node (ref "U3") (pin "1") (pinfunction "OUTA_1") (pintype "output"))
      (node (ref "U3") (pin "2") (pinfunction "INA-_2") (pintype "input"))
    )
    (net (code "102") (name "Net-(U4-FB)") (class "Default")
      (node (ref "C19") (pin "2") (pinfunction "2_2") (pintype "passive"))
      (node (ref "R15") (pin "1") (pinfunction "1_1") (pintype "passive"))
      (node (ref "R18") (pin "2") (pinfunction "2_2") (pintype "passive"))
      (node (ref "U4") (pin "8") (pinfunction "FB_8") (pintype "input"))
    )
    (net (code "103") (name "Net-(U4-L1)") (class "Default")
      (node (ref "L1") (pin "1") (pinfunction "1_1") (pintype "passive"))
      (node (ref "U4") (pin "1") (pinfunction "L1_1") (pintype "input"))
    )
    (net (code "104") (name "Net-(U4-L2)") (class "Default")
      (node (ref "L1") (pin "2") (pinfunction "2_2") (pintype "passive"))
      (node (ref "U4") (pin "10") (pinfunction "L2_10") (pintype "input"))
    )
    (net (code "105") (name "Net-(U4-PG)") (class "Default")
      (node (ref "R16") (pin "1") (pinfunction "1_1") (pintype "passive"))
      (node (ref "U4") (pin "5") (pinfunction "PG_5") (pintype "output"))
    )
    (net (code "106") (name "Net-(U4-VAUX)") (class "Default")
      (node (ref "C18") (pin "2") (pinfunction "2_2") (pintype "passive"))
      (node (ref "U4") (pin "6") (pinfunction "VAUX_6") (pintype "passive"))
    )
    (net (code "107") (name "unconnected-(C_test3-Pad2)") (class "Default")
      (node (ref "C_test3") (pin "2") (pinfunction "2_2") (pintype "passive"))
    )
    (net (code "108") (name "unconnected-(C_test4-Pad2)") (class "Default")
      (node (ref "C_test4") (pin "2") (pinfunction "2_2") (pintype "passive"))
    )
    (net (code "109") (name "unconnected-(C_test5-Pad1)") (class "Default")
      (node (ref "C_test5") (pin "1") (pinfunction "1_1") (pintype "passive"))
    )
    (net (code "110") (name "unconnected-(C_test6-Pad1)") (class "Default")
      (node (ref "C_test6") (pin "1") (pinfunction "1_1") (pintype "passive"))
    )
    (net (code "111") (name "unconnected-(D1_3-NC-Pad2)") (class "Default")
      (node (ref "D1_3") (pin "2") (pinfunction "NC_2") (pintype "passive"))
    )
    (net (code "112") (name "unconnected-(D1_4-NC-Pad2)") (class "Default")
      (node (ref "D1_4") (pin "2") (pinfunction "NC_2") (pintype "passive"))
    )
    (net (code "113") (name "unconnected-(D1_5-NC-Pad2)") (class "Default")
      (node (ref "D1_5") (pin "2") (pinfunction "NC_2") (pintype "passive"))
    )
    (net (code "114") (name "unconnected-(D1_6-NC-Pad2)") (class "Default")
      (node (ref "D1_6") (pin "2") (pinfunction "NC_2") (pintype "passive"))
    )
    (net (code "115") (name "unconnected-(D2_3-NC-Pad2)") (class "Default")
      (node (ref "D2_3") (pin "2") (pinfunction "NC_2") (pintype "passive"))
    )
    (net (code "116") (name "unconnected-(D2_4-NC-Pad2)") (class "Default")
      (node (ref "D2_4") (pin "2") (pinfunction "NC_2") (pintype "passive"))
    )
    (net (code "117") (name "unconnected-(D2_5-NC-Pad2)") (class "Default")
      (node (ref "D2_5") (pin "2") (pinfunction "NC_2") (pintype "passive"))
    )
    (net (code "118") (name "unconnected-(D2_6-NC-Pad2)") (class "Default")
      (node (ref "D2_6") (pin "2") (pinfunction "NC_2") (pintype "passive"))
    )
    (net (code "119") (name "unconnected-(H1-D+-Pad3)") (class "Default")
      (node (ref "H1") (pin "3") (pinfunction "D+_3") (pintype "passive"))
    )
    (net (code "120") (name "unconnected-(H1-D--Pad2)") (class "Default")
      (node (ref "H1") (pin "2") (pinfunction "D-_2") (pintype "passive"))
    )
    (net (code "121") (name "unconnected-(IC2-FC-Pad1)") (class "Default")
      (node (ref "IC2") (pin "1") (pinfunction "FC_1") (pintype "passive"))
    )
    (net (code "122") (name "unconnected-(IC2-LV-Pad6)") (class "Default")
      (node (ref "IC2") (pin "6") (pinfunction "LV_6") (pintype "passive"))
    )
    (net (code "123") (name "unconnected-(IC2-OSC-Pad7)") (class "Default")
      (node (ref "IC2") (pin "7") (pinfunction "OSC_7") (pintype "passive"))
    )
    (net (code "124") (name "unconnected-(J7-DAT1-Pad8)") (class "Default")
      (node (ref "J7") (pin "8") (pinfunction "DAT1_8") (pintype "bidirectional"))
    )
    (net (code "125") (name "unconnected-(J7-DAT2-Pad1)") (class "Default")
      (node (ref "J7") (pin "1") (pinfunction "DAT2_1") (pintype "bidirectional"))
    )
    (net (code "126") (name "unconnected-(M1-P0.02-Pad15)") (class "Default")
      (node (ref "M1") (pin "15") (pinfunction "P0.02_15") (pintype "passive"))
    )
    (net (code "127") (name "unconnected-(M1-P0.03-Pad16)") (class "Default")
      (node (ref "M1") (pin "16") (pinfunction "P0.03_16") (pintype "passive"))
    )
    (net (code "128") (name "unconnected-(M1-P0.05-Pad18)") (class "Default")
      (node (ref "M1") (pin "18") (pinfunction "P0.05_18") (pintype "passive"))
    )
    (net (code "129") (name "unconnected-(M1-P0.06-Pad19)") (class "Default")
      (node (ref "M1") (pin "19") (pinfunction "P0.06_19") (pintype "passive"))
    )
    (net (code "130") (name "unconnected-(M1-P0.07-Pad20)") (class "Default")
      (node (ref "M1") (pin "20") (pinfunction "P0.07_20") (pintype "passive"))
    )
    (net (code "131") (name "unconnected-(M1-P0.08-Pad21)") (class "Default")
      (node (ref "M1") (pin "21") (pinfunction "P0.08_21") (pintype "passive"))
    )
    (net (code "132") (name "unconnected-(M1-P0.09-Pad22)") (class "Default")
      (node (ref "M1") (pin "22") (pinfunction "P0.09_22") (pintype "passive"))
    )
    (net (code "133") (name "unconnected-(M1-P0.10-Pad23)") (class "Default")
      (node (ref "M1") (pin "23") (pinfunction "P0.10_23") (pintype "passive"))
    )
    (net (code "134") (name "unconnected-(M1-P0.19-Pad33)") (class "Default")
      (node (ref "M1") (pin "33") (pinfunction "P0.19_33") (pintype "passive"))
    )
    (net (code "135") (name "unconnected-(M1-P0.21{slash}RESET-Pad35)") (class "Default")
      (node (ref "M1") (pin "35") (pinfunction "P0.21/RESET_35") (pintype "passive"))
    )
    (net (code "136") (name "unconnected-(M1-P0.23-Pad41)") (class "Default")
      (node (ref "M1") (pin "41") (pinfunction "P0.23_41") (pintype "passive"))
    )
    (net (code "137") (name "unconnected-(M1-P0.24-Pad40)") (class "Default")
      (node (ref "M1") (pin "40") (pinfunction "P0.24_40") (pintype "passive"))
    )
    (net (code "138") (name "unconnected-(M1-P0.25-Pad2)") (class "Default")
      (node (ref "M1") (pin "2") (pinfunction "P0.25_2") (pintype "passive"))
    )
    (net (code "139") (name "unconnected-(M1-P0.26-Pad3)") (class "Default")
      (node (ref "M1") (pin "3") (pinfunction "P0.26_3") (pintype "passive"))
    )
    (net (code "140") (name "unconnected-(M1-P0.27-Pad4)") (class "Default")
      (node (ref "M1") (pin "4") (pinfunction "P0.27_4") (pintype "passive"))
    )
    (net (code "141") (name "unconnected-(M1-P0.28-Pad5)") (class "Default")
      (node (ref "M1") (pin "5") (pinfunction "P0.28_5") (pintype "passive"))
    )
    (net (code "142") (name "unconnected-(M1-P0.29-Pad6)") (class "Default")
      (node (ref "M1") (pin "6") (pinfunction "P0.29_6") (pintype "passive"))
    )
    (net (code "143") (name "unconnected-(M1-P0.30-Pad7)") (class "Default")
      (node (ref "M1") (pin "7") (pinfunction "P0.30_7") (pintype "passive"))
    )
    (net (code "144") (name "unconnected-(M1-P0.31-Pad8)") (class "Default")
      (node (ref "M1") (pin "8") (pinfunction "P0.31_8") (pintype "passive"))
    )
    (net (code "145") (name "unconnected-(S1-ON_1-Pad1)") (class "Default")
      (node (ref "S1") (pin "1") (pinfunction "ON_1_1") (pintype "passive"))
    )
    (net (code "146") (name "unconnected-(U2-CLK-Pad37)") (class "Default")
      (node (ref "U2") (pin "37") (pinfunction "CLK_37") (pintype "input+no_connect"))
    )
    (net (code "147") (name "unconnected-(U2-IN5N-Pad7)") (class "Default")
      (node (ref "U2") (pin "7") (pinfunction "IN5N_7") (pintype "input+no_connect"))
    )
    (net (code "148") (name "unconnected-(U2-IN5P-Pad8)") (class "Default")
      (node (ref "U2") (pin "8") (pinfunction "IN5P_8") (pintype "input+no_connect"))
    )
    (net (code "149") (name "unconnected-(U2-IN6N-Pad5)") (class "Default")
      (node (ref "U2") (pin "5") (pinfunction "IN6N_5") (pintype "input+no_connect"))
    )
    (net (code "150") (name "unconnected-(U2-IN6P-Pad6)") (class "Default")
      (node (ref "U2") (pin "6") (pinfunction "IN6P_6") (pintype "input+no_connect"))
    )
    (net (code "151") (name "unconnected-(U2-IN7N-Pad3)") (class "Default")
      (node (ref "U2") (pin "3") (pinfunction "IN7N_3") (pintype "input+no_connect"))
    )
    (net (code "152") (name "unconnected-(U2-IN7P-Pad4)") (class "Default")
      (node (ref "U2") (pin "4") (pinfunction "IN7P_4") (pintype "input+no_connect"))
    )
    (net (code "153") (name "unconnected-(U2-IN8N-Pad1)") (class "Default")
      (node (ref "U2") (pin "1") (pinfunction "IN8N_1") (pintype "input+no_connect"))
    )
    (net (code "154") (name "unconnected-(U2-IN8P-Pad2)") (class "Default")
      (node (ref "U2") (pin "2") (pinfunction "IN8P_2") (pintype "input+no_connect"))
    )
    (net (code "155") (name "unconnected-(U2-NC-Pad27)") (class "Default")
      (node (ref "U2") (pin "27") (pinfunction "NC_27") (pintype "passive"))
    )
    (net (code "156") (name "unconnected-(U2-NC-Pad29)") (class "Default")
      (node (ref "U2") (pin "29") (pinfunction "NC_29") (pintype "passive"))
    )
    (net (code "157") (name "unconnected-(U2-RESERVED-Pad64)") (class "Default")
      (node (ref "U2") (pin "64") (pinfunction "RESERVED_64") (pintype "output"))
    )
    (net (code "158") (name "unconnected-(U2-SRB2-Pad18)") (class "Default")
      (node (ref "U2") (pin "18") (pinfunction "SRB2_18") (pintype "bidirectional+no_connect"))
    )
  )
)
